# ACB-Light-R1_0-J03.net
KiCad netlist of a schematic drawn in EAGLE
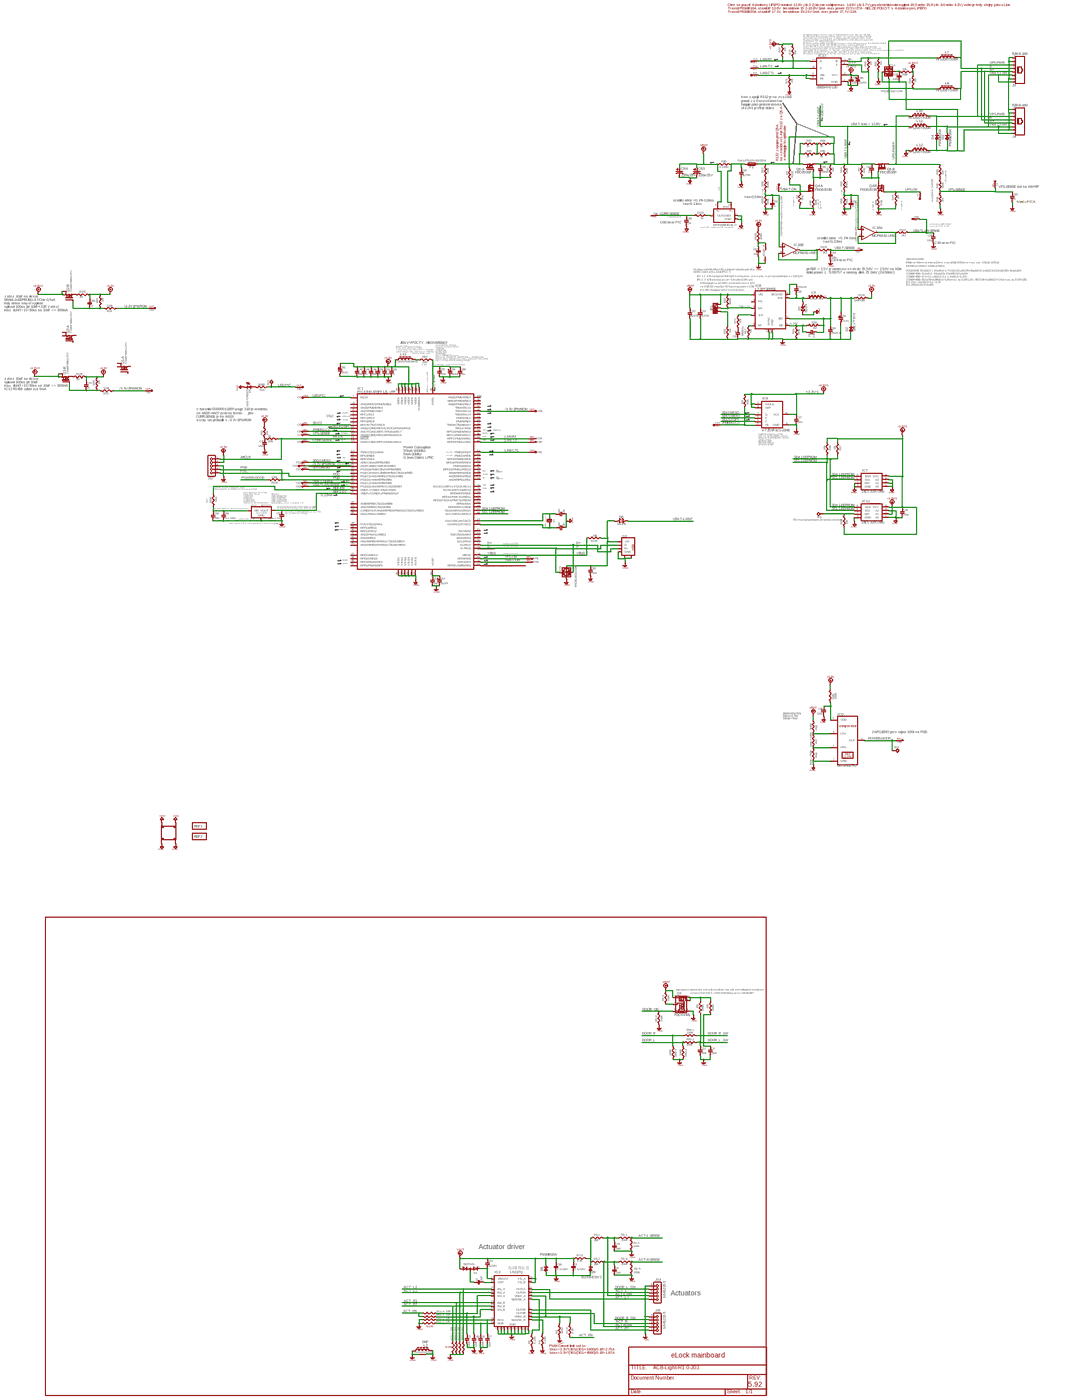
[diagram p0: schematic, sheet 1, overview]
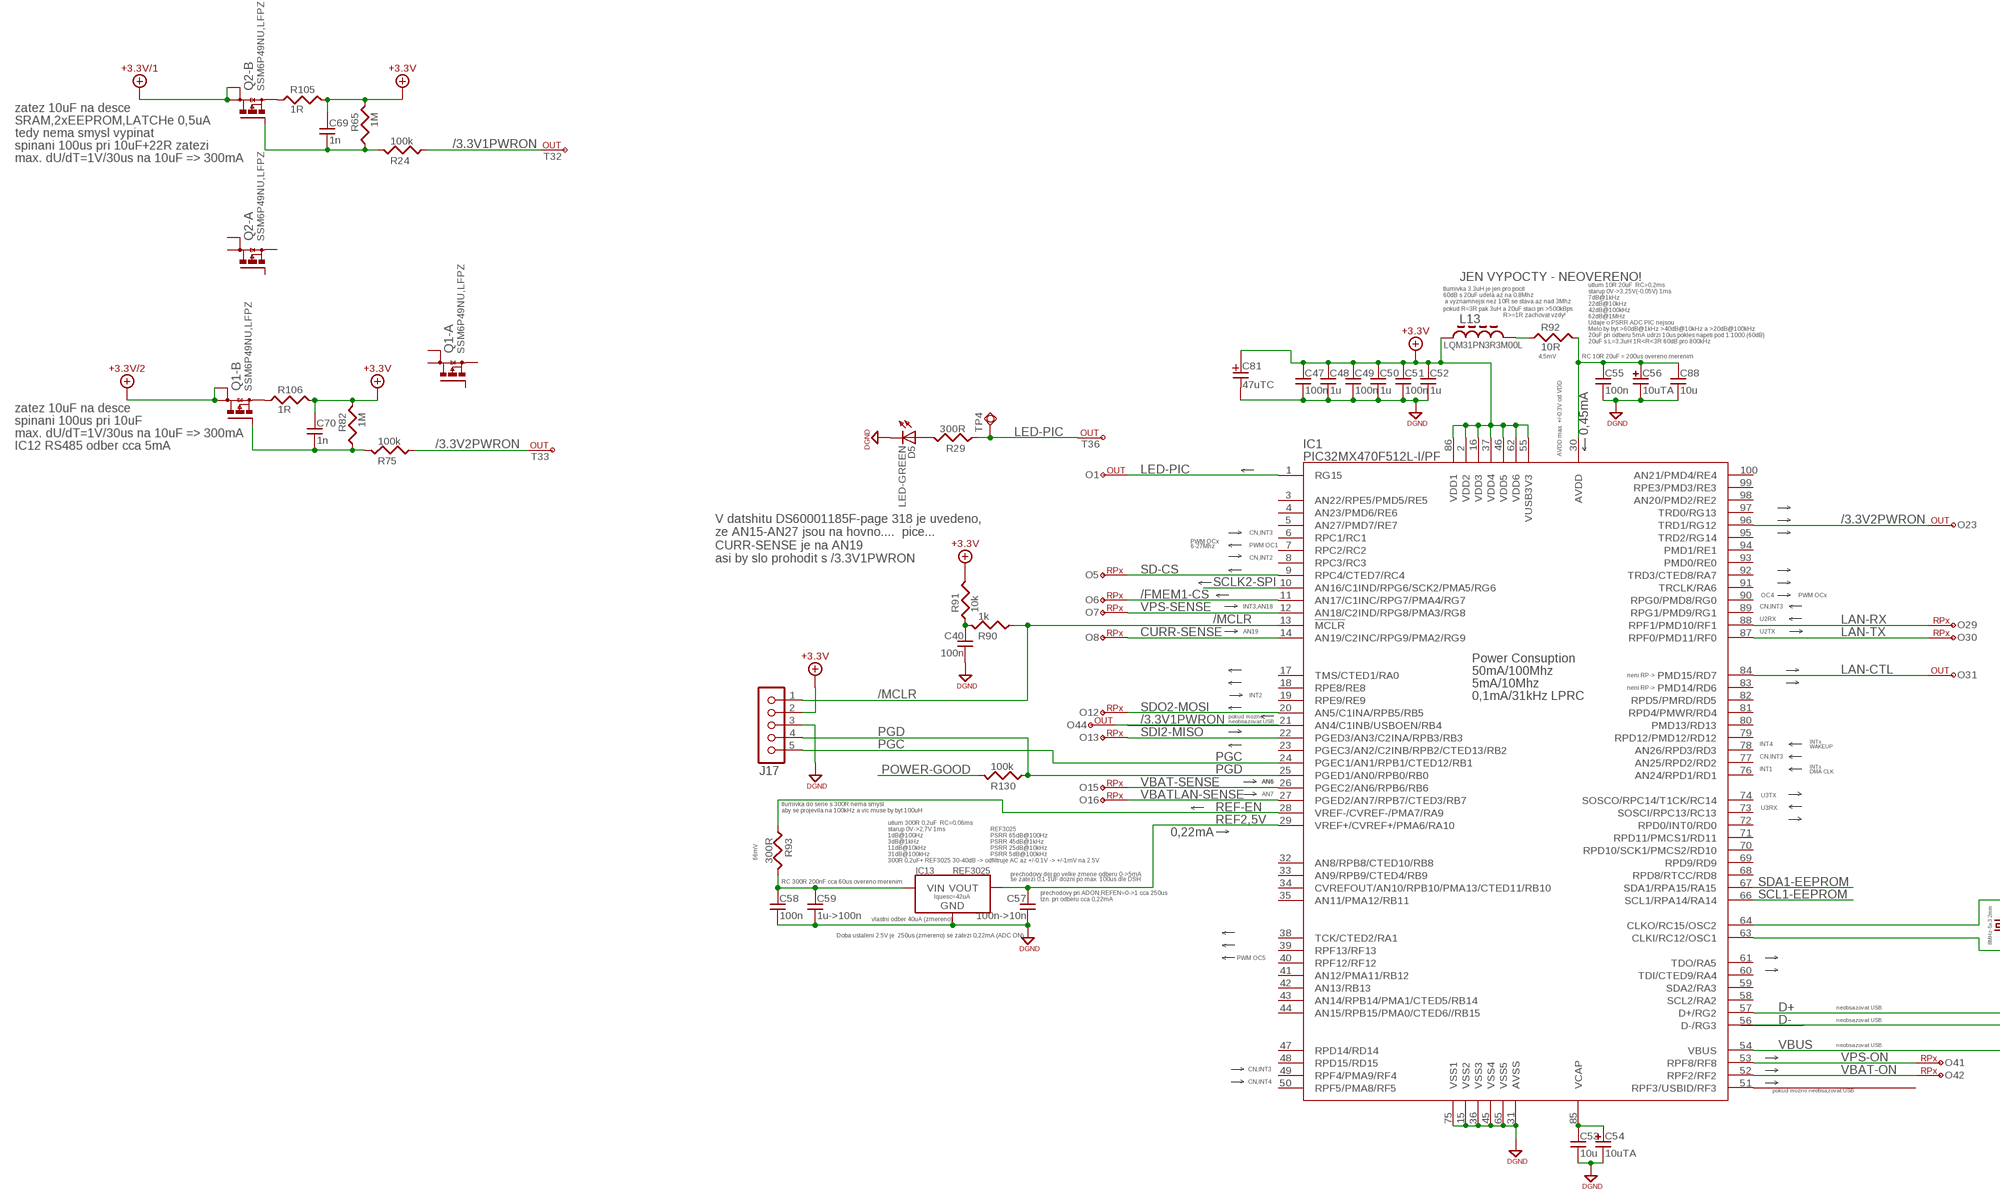
[diagram p1: schematic, sheet 1, part 1 of 5]
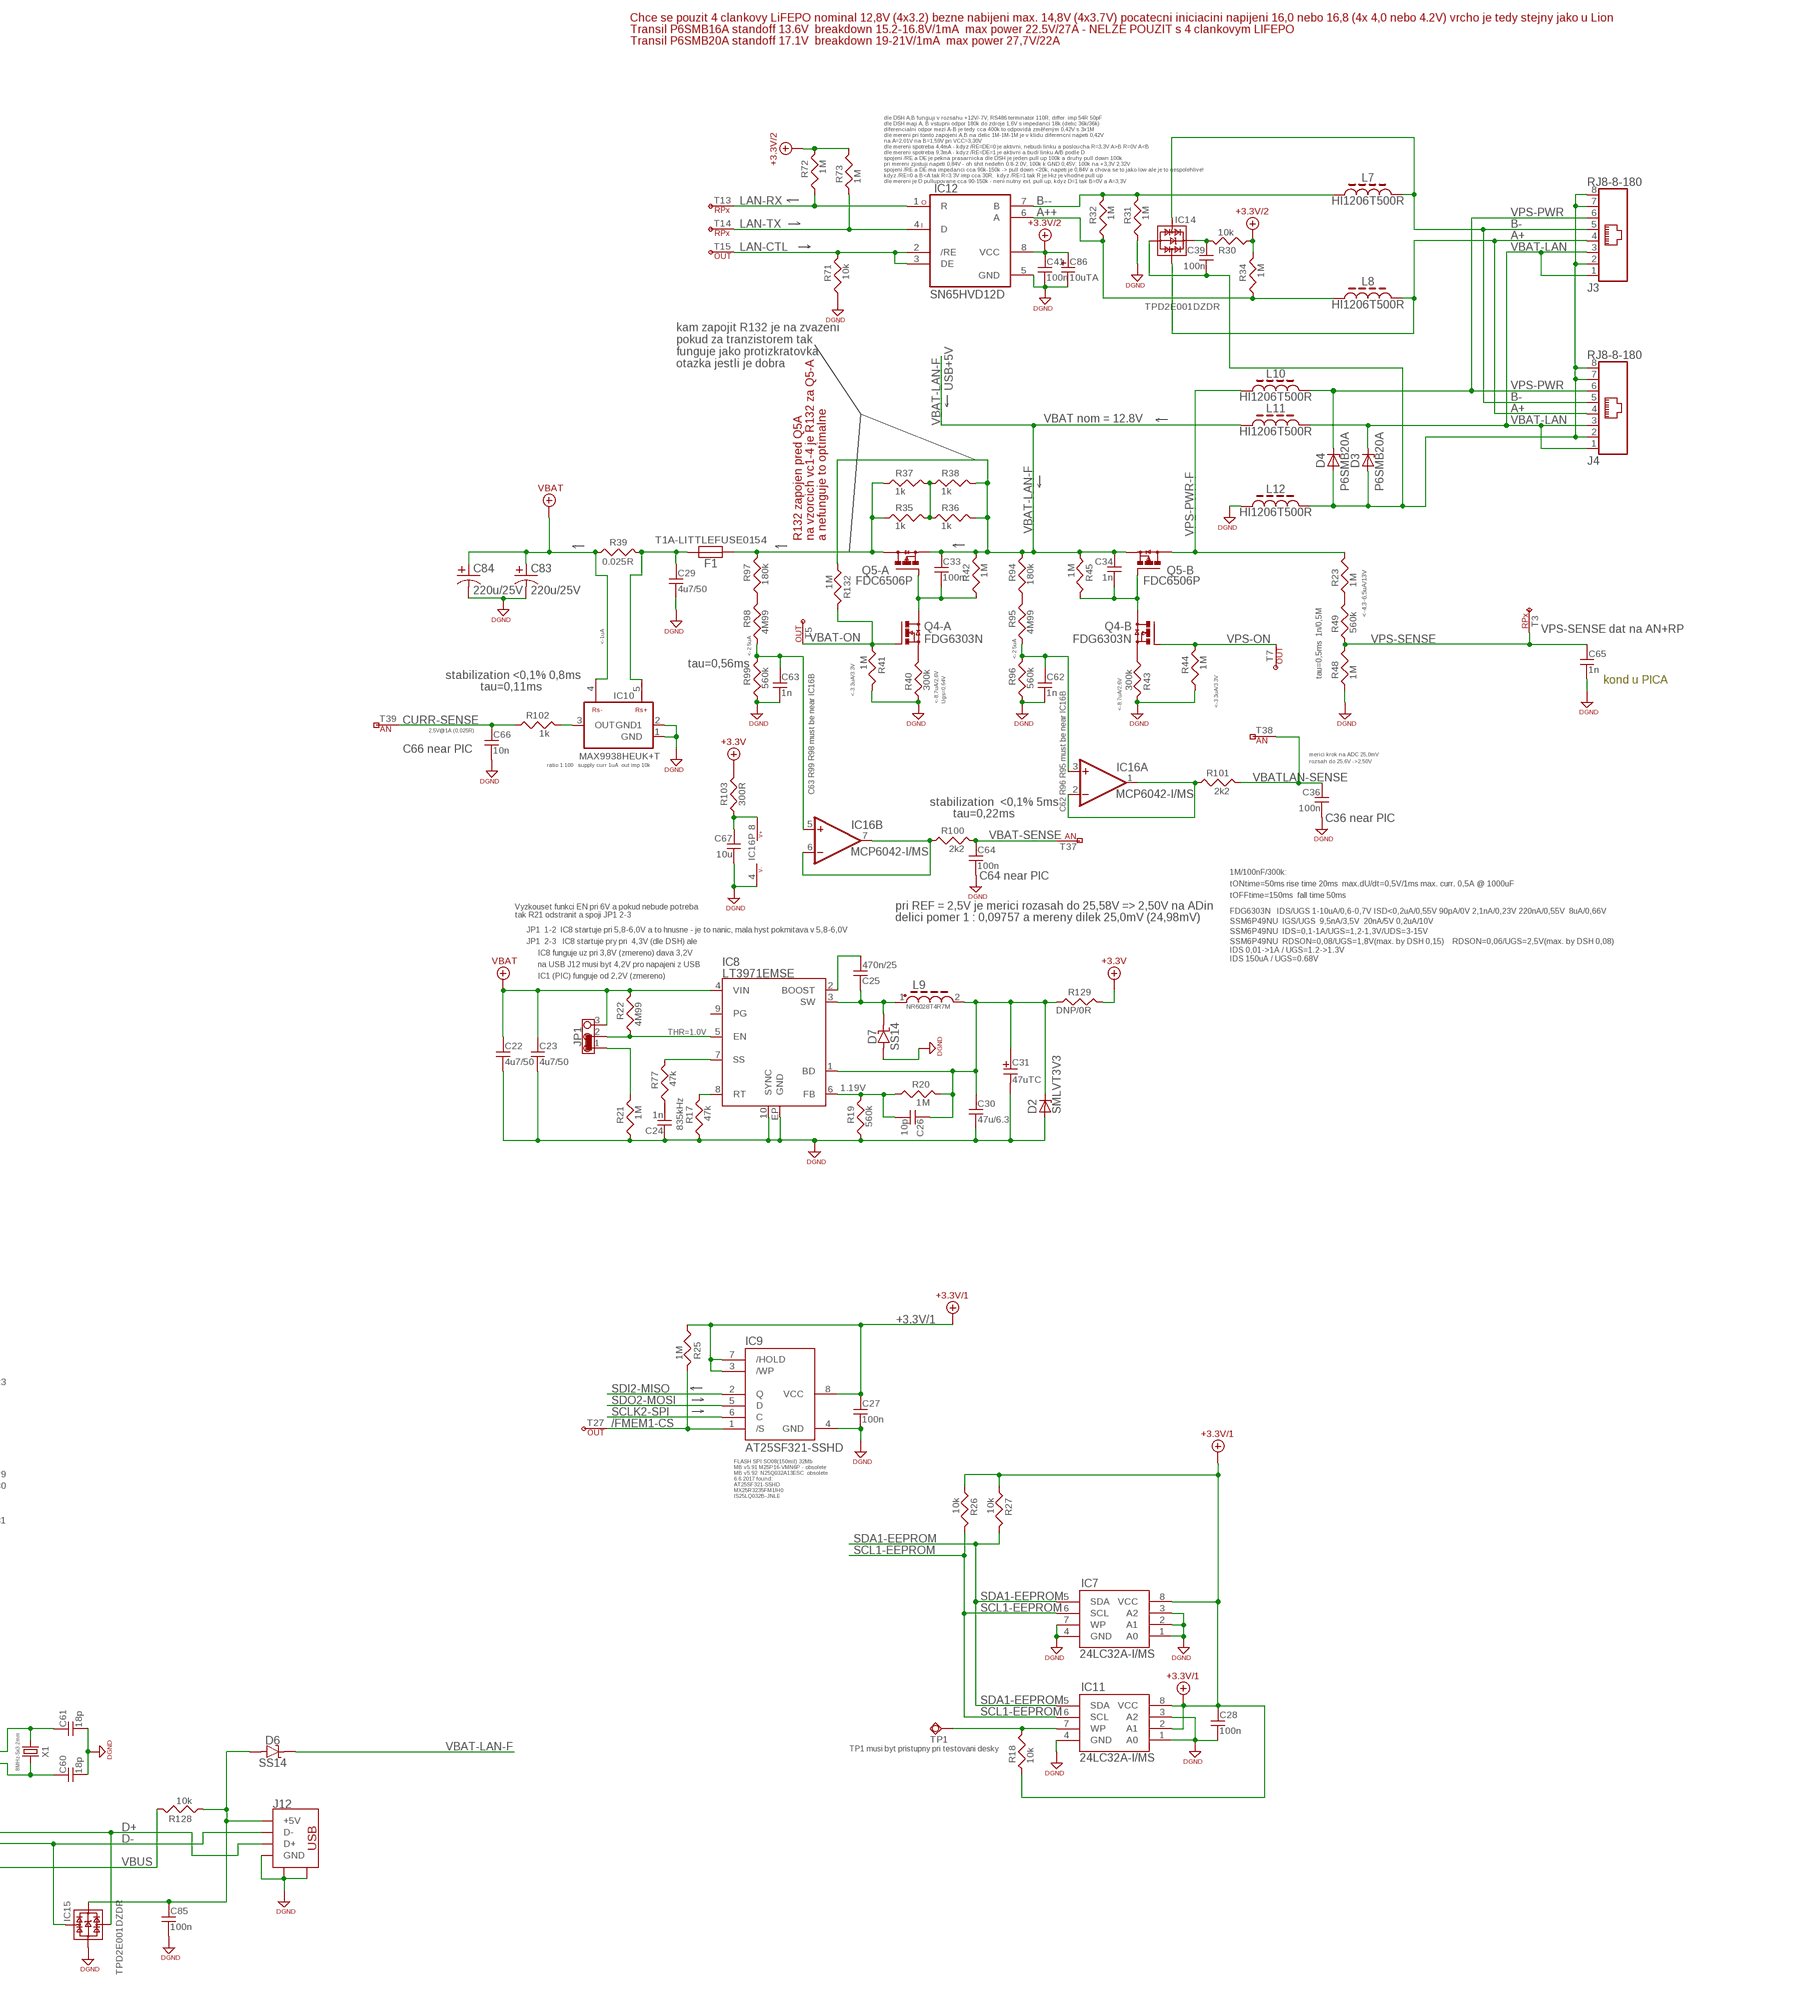
[diagram p2: schematic, sheet 1, part 2 of 5]
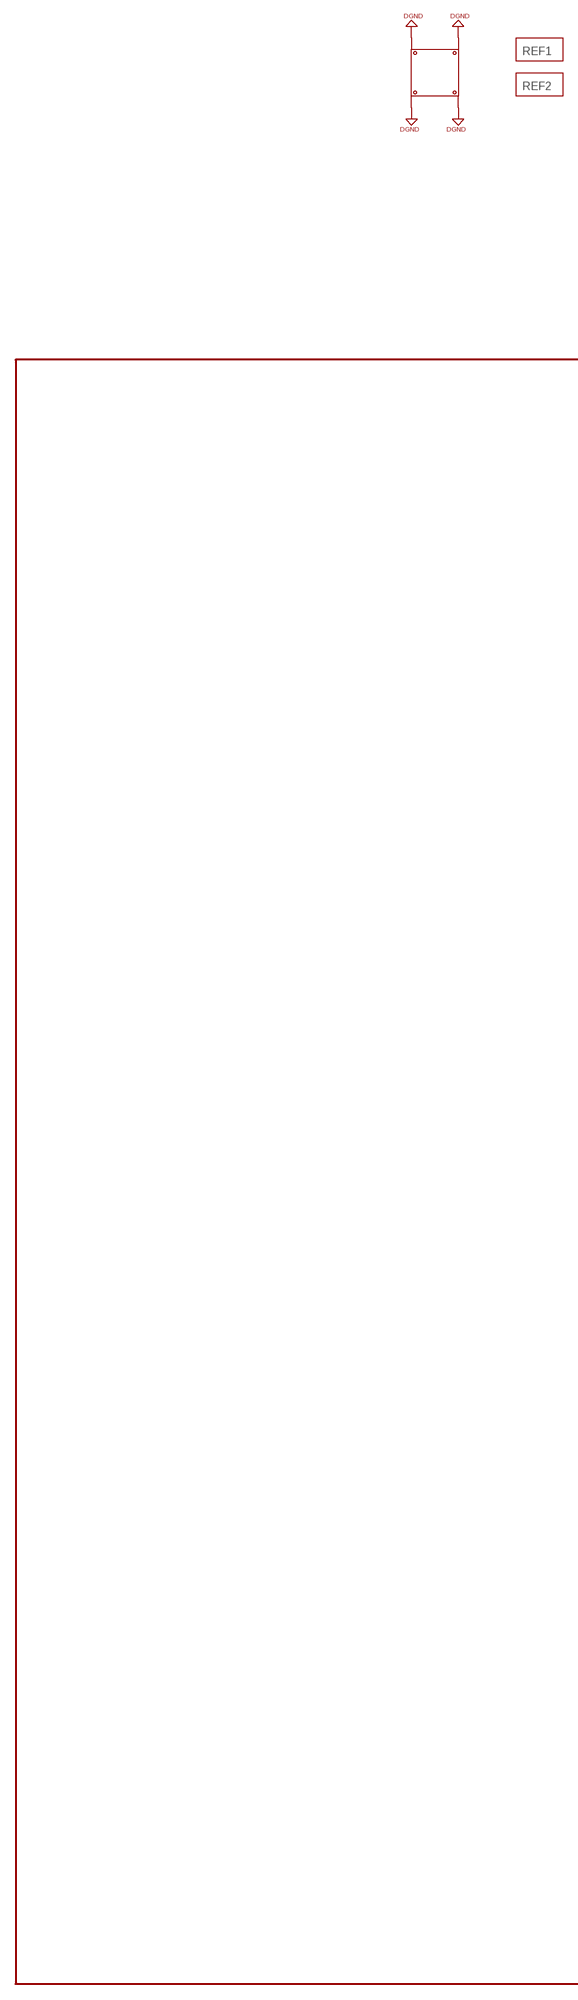
[diagram p3: schematic, sheet 1, part 3 of 5]
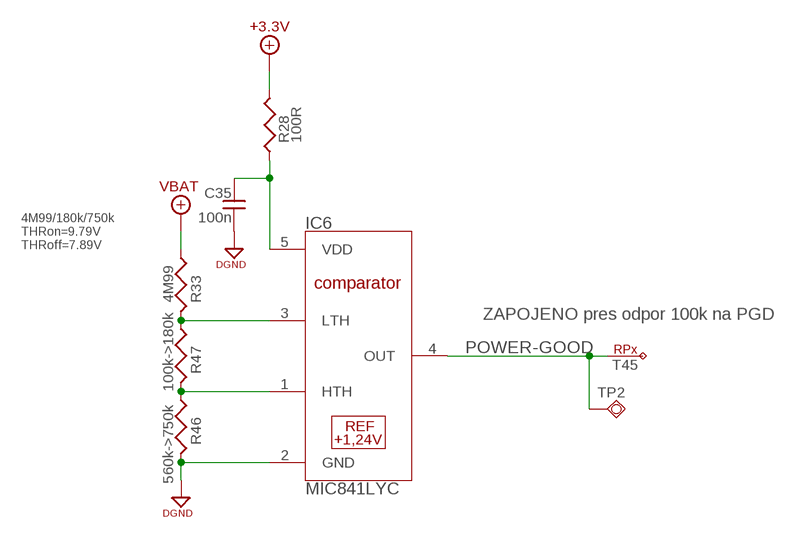
[diagram p4: schematic, sheet 1, part 4 of 5]
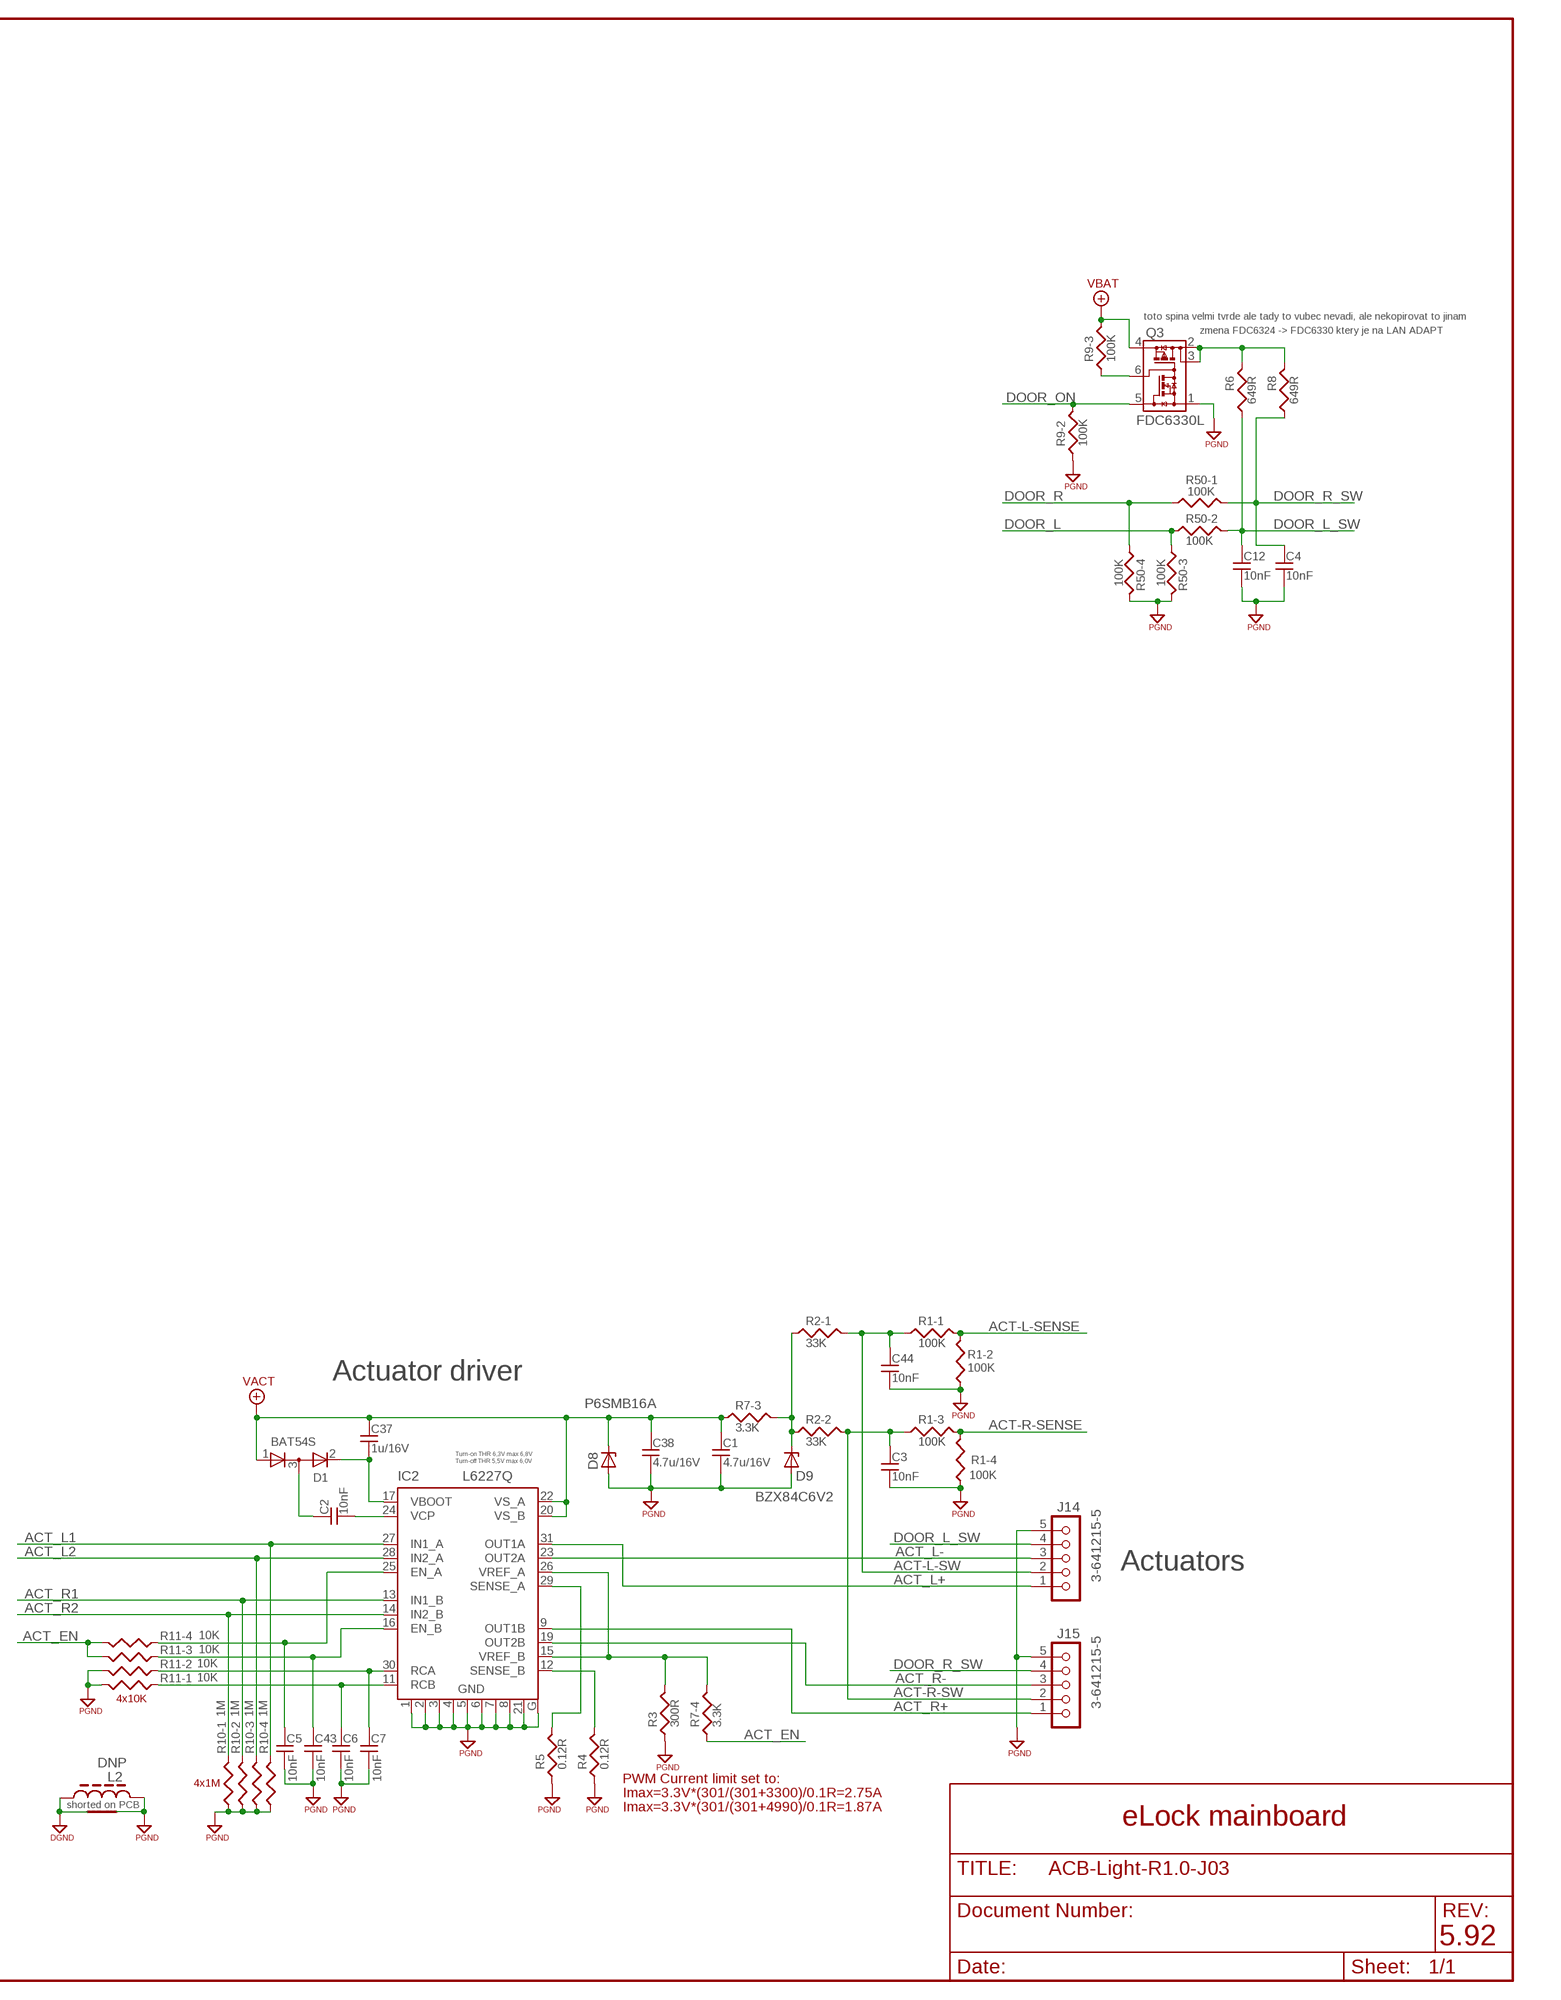
[diagram p5: schematic, sheet 1, part 5 of 5]

(export (version "E")
  (design (tool "Eeschema 10.0.6"))
  (components
    (comp (ref "C1")
      (value "4.7u/16V")
      (footprint "eagle-import:0805")
      (libsource (lib "eagle-import") (part "C-0805"))
    )
    (comp (ref "C2")
      (value "10nF")
      (footprint "eagle-import:0603")
      (libsource (lib "eagle-import") (part "C-0603"))
    )
    (comp (ref "C3")
      (value "10nF")
      (footprint "eagle-import:0603")
      (libsource (lib "eagle-import") (part "C-0603"))
    )
    (comp (ref "C4")
      (value "10nF")
      (footprint "eagle-import:0603")
      (libsource (lib "eagle-import") (part "C-0603"))
    )
    (comp (ref "C5")
      (value "10nF")
      (footprint "eagle-import:0603")
      (libsource (lib "eagle-import") (part "C-0603"))
    )
    (comp (ref "C6")
      (value "10nF")
      (footprint "eagle-import:0603")
      (libsource (lib "eagle-import") (part "C-0603"))
    )
    (comp (ref "C7")
      (value "10nF")
      (footprint "eagle-import:0603")
      (libsource (lib "eagle-import") (part "C-0603"))
    )
    (comp (ref "C12")
      (value "10nF")
      (footprint "eagle-import:0603")
      (libsource (lib "eagle-import") (part "C-0603"))
    )
    (comp (ref "C22")
      (value "4u7/50")
      (footprint "eagle-import:1206")
      (libsource (lib "eagle-import") (part "C-1206"))
    )
    (comp (ref "C23")
      (value "4u7/50")
      (footprint "eagle-import:1206")
      (libsource (lib "eagle-import") (part "C-1206"))
    )
    (comp (ref "C24")
      (value "1n")
      (footprint "eagle-import:0603")
      (libsource (lib "eagle-import") (part "C-0603"))
    )
    (comp (ref "C25")
      (value "470n/25")
      (footprint "eagle-import:0603")
      (libsource (lib "eagle-import") (part "C-0603"))
    )
    (comp (ref "C26")
      (value "10p")
      (footprint "eagle-import:0603")
      (libsource (lib "eagle-import") (part "C-0603"))
    )
    (comp (ref "C27")
      (value "100n")
      (footprint "eagle-import:0603")
      (libsource (lib "eagle-import") (part "C-0603"))
    )
    (comp (ref "C28")
      (value "100n")
      (footprint "eagle-import:0603")
      (libsource (lib "eagle-import") (part "C-0603"))
    )
    (comp (ref "C29")
      (value "4u7/50")
      (footprint "eagle-import:1206")
      (libsource (lib "eagle-import") (part "C-1206"))
    )
    (comp (ref "C30")
      (value "47u/6.3")
      (footprint "eagle-import:1206")
      (libsource (lib "eagle-import") (part "C-1206"))
    )
    (comp (ref "C31")
      (value "47uTC")
      (footprint "eagle-import:CT-C")
      (libsource (lib "eagle-import") (part "CT-C"))
    )
    (comp (ref "C33")
      (value "100n")
      (footprint "eagle-import:0603")
      (libsource (lib "eagle-import") (part "C-0603"))
    )
    (comp (ref "C34")
      (value "1n")
      (footprint "eagle-import:0603")
      (libsource (lib "eagle-import") (part "C-0603"))
    )
    (comp (ref "C35")
      (value "100n")
      (footprint "eagle-import:0603")
      (libsource (lib "eagle-import") (part "C-0603"))
    )
    (comp (ref "C36")
      (value "100n")
      (footprint "eagle-import:0603")
      (libsource (lib "eagle-import") (part "C-0603"))
    )
    (comp (ref "C37")
      (value "1u/16V")
      (footprint "eagle-import:0603")
      (libsource (lib "eagle-import") (part "C-0603"))
    )
    (comp (ref "C38")
      (value "4.7u/16V")
      (footprint "eagle-import:0805")
      (libsource (lib "eagle-import") (part "C-0805"))
    )
    (comp (ref "C39")
      (value "100n")
      (footprint "eagle-import:0603")
      (libsource (lib "eagle-import") (part "C-0603"))
    )
    (comp (ref "C40")
      (value "100n")
      (footprint "eagle-import:0603")
      (libsource (lib "eagle-import") (part "C-0603"))
    )
    (comp (ref "C41")
      (value "100n")
      (footprint "eagle-import:0603")
      (libsource (lib "eagle-import") (part "C-0603"))
    )
    (comp (ref "C43")
      (value "10nF")
      (footprint "eagle-import:0603")
      (libsource (lib "eagle-import") (part "C-0603"))
    )
    (comp (ref "C44")
      (value "10nF")
      (footprint "eagle-import:0603")
      (libsource (lib "eagle-import") (part "C-0603"))
    )
    (comp (ref "C47")
      (value "100n")
      (footprint "eagle-import:0603")
      (libsource (lib "eagle-import") (part "C-0603"))
    )
    (comp (ref "C48")
      (value "1u")
      (footprint "eagle-import:0603")
      (libsource (lib "eagle-import") (part "C-0603"))
    )
    (comp (ref "C49")
      (value "100n")
      (footprint "eagle-import:0603")
      (libsource (lib "eagle-import") (part "C-0603"))
    )
    (comp (ref "C50")
      (value "1u")
      (footprint "eagle-import:0603")
      (libsource (lib "eagle-import") (part "C-0603"))
    )
    (comp (ref "C51")
      (value "100n")
      (footprint "eagle-import:0603")
      (libsource (lib "eagle-import") (part "C-0603"))
    )
    (comp (ref "C52")
      (value "1u")
      (footprint "eagle-import:0603")
      (libsource (lib "eagle-import") (part "C-0603"))
    )
    (comp (ref "C53")
      (value "10u")
      (footprint "eagle-import:0603")
      (libsource (lib "eagle-import") (part "C-0603"))
    )
    (comp (ref "C54")
      (value "10uTA")
      (footprint "eagle-import:1206-POL-C")
      (libsource (lib "eagle-import") (part "CT-1206"))
    )
    (comp (ref "C55")
      (value "100n")
      (footprint "eagle-import:0603")
      (libsource (lib "eagle-import") (part "C-0603"))
    )
    (comp (ref "C56")
      (value "10uTA")
      (footprint "eagle-import:1206-POL-C")
      (libsource (lib "eagle-import") (part "CT-1206"))
    )
    (comp (ref "C57")
      (value "100n->10n")
      (footprint "eagle-import:0603")
      (libsource (lib "eagle-import") (part "C-0603"))
    )
    (comp (ref "C58")
      (value "100n")
      (footprint "eagle-import:0603")
      (libsource (lib "eagle-import") (part "C-0603"))
    )
    (comp (ref "C59")
      (value "1u->100n")
      (footprint "eagle-import:0603")
      (libsource (lib "eagle-import") (part "C-0603"))
    )
    (comp (ref "C60")
      (value "18p")
      (footprint "eagle-import:0603")
      (libsource (lib "eagle-import") (part "C-0603"))
    )
    (comp (ref "C61")
      (value "18p")
      (footprint "eagle-import:0603")
      (libsource (lib "eagle-import") (part "C-0603"))
    )
    (comp (ref "C62")
      (value "1n")
      (footprint "eagle-import:0603")
      (libsource (lib "eagle-import") (part "C-0603"))
    )
    (comp (ref "C63")
      (value "1n")
      (footprint "eagle-import:0603")
      (libsource (lib "eagle-import") (part "C-0603"))
    )
    (comp (ref "C64")
      (value "100n")
      (footprint "eagle-import:0603")
      (libsource (lib "eagle-import") (part "C-0603"))
    )
    (comp (ref "C65")
      (value "1n")
      (footprint "eagle-import:0603")
      (libsource (lib "eagle-import") (part "C-0603"))
    )
    (comp (ref "C66")
      (value "10n")
      (footprint "eagle-import:0603")
      (libsource (lib "eagle-import") (part "C-0603"))
    )
    (comp (ref "C67")
      (value "10u")
      (footprint "eagle-import:0603")
      (libsource (lib "eagle-import") (part "C-0603"))
    )
    (comp (ref "C69")
      (value "1n")
      (footprint "eagle-import:0603")
      (libsource (lib "eagle-import") (part "C-0603"))
    )
    (comp (ref "C70")
      (value "1n")
      (footprint "eagle-import:0603")
      (libsource (lib "eagle-import") (part "C-0603"))
    )
    (comp (ref "C81")
      (value "47uTC")
      (footprint "eagle-import:CT-C")
      (libsource (lib "eagle-import") (part "CT-C"))
    )
    (comp (ref "C83")
      (value "220u/25V")
      (footprint "eagle-import:CAP_8MM_DIA_SMT")
      (libsource (lib "eagle-import") (part "CAP-ELEC-SMD-8MM"))
    )
    (comp (ref "C84")
      (value "220u/25V")
      (footprint "eagle-import:CAP_8MM_DIA_SMT")
      (libsource (lib "eagle-import") (part "CAP-ELEC-SMD-8MM"))
    )
    (comp (ref "C85")
      (value "100n")
      (footprint "eagle-import:0603")
      (libsource (lib "eagle-import") (part "C-0603"))
    )
    (comp (ref "C86")
      (value "10uTA")
      (footprint "eagle-import:1206-POL-C")
      (libsource (lib "eagle-import") (part "CT-1206"))
    )
    (comp (ref "C88")
      (value "10u")
      (footprint "eagle-import:0603")
      (libsource (lib "eagle-import") (part "C-0603"))
    )
    (comp (ref "D1")
      (value "BAT54S")
      (footprint "eagle-import:SOT-23")
      (libsource (lib "eagle-import") (part "BAT54S"))
    )
    (comp (ref "D2")
      (value "SMLVT3V3")
      (footprint "eagle-import:SMA")
      (libsource (lib "eagle-import") (part "SMLVT3V3"))
    )
    (comp (ref "D3")
      (value "P6SMB20A")
      (footprint "eagle-import:SMB")
      (libsource (lib "eagle-import") (part "P6SMB"))
    )
    (comp (ref "D4")
      (value "P6SMB20A")
      (footprint "eagle-import:SMB")
      (libsource (lib "eagle-import") (part "P6SMB"))
    )
    (comp (ref "D5")
      (value "LED-GREEN")
      (footprint "eagle-import:0805-POL-D")
      (libsource (lib "eagle-import") (part "LED-0805"))
    )
    (comp (ref "D6")
      (value "SS14")
      (footprint "eagle-import:SMA")
      (libsource (lib "eagle-import") (part "DS-SMA"))
    )
    (comp (ref "D7")
      (value "SS14")
      (footprint "eagle-import:SMA")
      (libsource (lib "eagle-import") (part "DS-SMA"))
    )
    (comp (ref "D8")
      (value "P6SMB16A")
      (footprint "eagle-import:SMB")
      (libsource (lib "eagle-import") (part "P6SMB"))
    )
    (comp (ref "D9")
      (value "BZX84C6V2")
      (footprint "eagle-import:SOT-23")
      (libsource (lib "eagle-import") (part "BZX84C6V2"))
    )
    (comp (ref "F1")
      (value "T1A-LITTLEFUSE0154")
      (footprint "eagle-import:LITTLEFUSE0154")
      (libsource (lib "eagle-import") (part "POJISTKA-LITTLEFUSE0154"))
    )
    (comp (ref "IC1")
      (value "PIC32MX470F512L-I/PF")
      (footprint "eagle-import:TQFP100_14X14_0,5MM")
      (libsource (lib "eagle-import") (part "PIC32MX470F512L-I/PF"))
    )
    (comp (ref "IC2")
      (value "L6227Q")
      (footprint "eagle-import:SQFP-S-5X5-32")
      (libsource (lib "eagle-import") (part "L6227Q"))
    )
    (comp (ref "IC6")
      (value "MIC841LYC")
      (footprint "eagle-import:SC-70-5")
      (libsource (lib "eagle-import") (part "MIC841LYC"))
    )
    (comp (ref "IC7")
      (value "24LC32A-I/MS")
      (footprint "eagle-import:MSOP-08")
      (libsource (lib "eagle-import") (part "24-I/MS"))
    )
    (comp (ref "IC8")
      (value "LT3971EMSE")
      (footprint "eagle-import:MSOP10EXP")
      (libsource (lib "eagle-import") (part "LT3971EMSE"))
    )
    (comp (ref "IC9")
      (value "AT25SF321-SSHD")
      (footprint "eagle-import:SO-08")
      (libsource (lib "eagle-import") (part "M25P16-VMN6P"))
    )
    (comp (ref "IC10")
      (value "MAX9938HEUK+T")
      (footprint "eagle-import:SOT23-5")
      (libsource (lib "eagle-import") (part "TSM9938HEUK+T"))
    )
    (comp (ref "IC11")
      (value "24LC32A-I/MS")
      (footprint "eagle-import:MSOP-08")
      (libsource (lib "eagle-import") (part "24-I/MS"))
    )
    (comp (ref "IC12")
      (value "SN65HVD12D")
      (footprint "eagle-import:SO08")
      (libsource (lib "eagle-import") (part "SN65HVD3082ED"))
    )
    (comp (ref "IC13")
      (value "REF3025")
      (footprint "eagle-import:SOT23")
      (libsource (lib "eagle-import") (part "REF3025"))
    )
    (comp (ref "IC14")
      (value "TPD2E001DZDR")
      (footprint "eagle-import:SOT-143")
      (libsource (lib "eagle-import") (part "SR05.TCT"))
    )
    (comp (ref "IC15")
      (value "TPD2E001DZDR")
      (footprint "eagle-import:SOT-143")
      (libsource (lib "eagle-import") (part "SR05.TCT"))
    )
    (comp (ref "IC16")
      (value "MCP6042-I/MS")
      (footprint "eagle-import:MSOP-08")
      (libsource (lib "eagle-import") (part "MCP6042-I/MS"))
    )
    (comp (ref "J3")
      (value "RJ8-8-180")
      (footprint "eagle-import:RJ8-8-180")
      (libsource (lib "eagle-import") (part "RJ8-8-180"))
    )
    (comp (ref "J4")
      (value "RJ8-8-180")
      (footprint "eagle-import:RJ8-8-180")
      (libsource (lib "eagle-import") (part "RJ8-8-180"))
    )
    (comp (ref "J12")
      (value "USB_A_180")
      (footprint "eagle-import:USB_B_180")
      (libsource (lib "eagle-import") (part "USB_B_180"))
    )
    (comp (ref "J14")
      (value "3-641215-5")
      (footprint "eagle-import:3-641215-5")
      (libsource (lib "eagle-import") (part "3-641215-5"))
    )
    (comp (ref "J15")
      (value "3-641215-5")
      (footprint "eagle-import:3-641215-5")
      (libsource (lib "eagle-import") (part "3-641215-5"))
    )
    (comp (ref "J17")
      (value "DNP-open-hole")
      (footprint "eagle-import:MA05-1")
      (libsource (lib "eagle-import") (part "MA05-1"))
    )
    (comp (ref "JP1")
      (value "JP3CLOSE12")
      (footprint "eagle-import:JP3CLOSE12")
      (libsource (lib "eagle-import") (part "JP3CLOSE12"))
    )
    (comp (ref "L2")
      (value "DNP")
      (footprint "eagle-import:0805-0RTOP")
      (libsource (lib "eagle-import") (part "L-0805-0R"))
    )
    (comp (ref "L7")
      (value "HI1206T500R")
      (footprint "eagle-import:1206")
      (libsource (lib "eagle-import") (part "L-1206"))
    )
    (comp (ref "L8")
      (value "HI1206T500R")
      (footprint "eagle-import:1206")
      (libsource (lib "eagle-import") (part "L-1206"))
    )
    (comp (ref "L9")
      (value "NR6028T4R7M")
      (footprint "eagle-import:NR6028")
      (libsource (lib "eagle-import") (part "NR6028"))
    )
    (comp (ref "L10")
      (value "HI1206T500R")
      (footprint "eagle-import:1206")
      (libsource (lib "eagle-import") (part "L-1206"))
    )
    (comp (ref "L11")
      (value "HI1206T500R")
      (footprint "eagle-import:1206")
      (libsource (lib "eagle-import") (part "L-1206"))
    )
    (comp (ref "L12")
      (value "HI1206T500R")
      (footprint "eagle-import:1206")
      (libsource (lib "eagle-import") (part "L-1206"))
    )
    (comp (ref "L13")
      (value "LQM31PN3R3M00L")
      (footprint "eagle-import:1206")
      (libsource (lib "eagle-import") (part "L-1206"))
    )
    (comp (ref "O1")
      (value "PIC-OUT")
      (footprint "eagle-import:TEMP-PAD")
      (libsource (lib "eagle-import") (part "PIC-OUT"))
    )
    (comp (ref "O5")
      (value "PIC-RPX")
      (footprint "eagle-import:TEMP-PAD")
      (libsource (lib "eagle-import") (part "PIC-RPX"))
    )
    (comp (ref "O6")
      (value "PIC-RPX")
      (footprint "eagle-import:TEMP-PAD")
      (libsource (lib "eagle-import") (part "PIC-RPX"))
    )
    (comp (ref "O7")
      (value "PIC-RPX")
      (footprint "eagle-import:TEMP-PAD")
      (libsource (lib "eagle-import") (part "PIC-RPX"))
    )
    (comp (ref "O8")
      (value "PIC-RPX")
      (footprint "eagle-import:TEMP-PAD")
      (libsource (lib "eagle-import") (part "PIC-RPX"))
    )
    (comp (ref "O12")
      (value "PIC-RPX")
      (footprint "eagle-import:TEMP-PAD")
      (libsource (lib "eagle-import") (part "PIC-RPX"))
    )
    (comp (ref "O13")
      (value "PIC-RPX")
      (footprint "eagle-import:TEMP-PAD")
      (libsource (lib "eagle-import") (part "PIC-RPX"))
    )
    (comp (ref "O15")
      (value "PIC-RPX")
      (footprint "eagle-import:TEMP-PAD")
      (libsource (lib "eagle-import") (part "PIC-RPX"))
    )
    (comp (ref "O16")
      (value "PIC-RPX")
      (footprint "eagle-import:TEMP-PAD")
      (libsource (lib "eagle-import") (part "PIC-RPX"))
    )
    (comp (ref "O23")
      (value "PIC-OUT")
      (footprint "eagle-import:TEMP-PAD")
      (libsource (lib "eagle-import") (part "PIC-OUT"))
    )
    (comp (ref "O29")
      (value "PIC-RPX")
      (footprint "eagle-import:TEMP-PAD")
      (libsource (lib "eagle-import") (part "PIC-RPX"))
    )
    (comp (ref "O30")
      (value "PIC-RPX")
      (footprint "eagle-import:TEMP-PAD")
      (libsource (lib "eagle-import") (part "PIC-RPX"))
    )
    (comp (ref "O31")
      (value "PIC-OUT")
      (footprint "eagle-import:TEMP-PAD")
      (libsource (lib "eagle-import") (part "PIC-OUT"))
    )
    (comp (ref "O41")
      (value "PIC-RPX")
      (footprint "eagle-import:TEMP-PAD")
      (libsource (lib "eagle-import") (part "PIC-RPX"))
    )
    (comp (ref "O42")
      (value "PIC-RPX")
      (footprint "eagle-import:TEMP-PAD")
      (libsource (lib "eagle-import") (part "PIC-RPX"))
    )
    (comp (ref "O44")
      (value "PIC-OUT")
      (footprint "eagle-import:TEMP-PAD")
      (libsource (lib "eagle-import") (part "PIC-OUT"))
    )
    (comp (ref "PCB1")
      (value "PCB-ACB")
      (footprint "eagle-import:PCB-ACB")
      (libsource (lib "eagle-import") (part "PCB-ACB-1"))
    )
    (comp (ref "Q1")
      (value "SSM6P49NU,LFPZ")
      (footprint "eagle-import:MICRO_FET")
      (libsource (lib "eagle-import") (part "SSM6P49PZNU,LF"))
    )
    (comp (ref "Q2")
      (value "SSM6P49NU,LFPZ")
      (footprint "eagle-import:MICRO_FET")
      (libsource (lib "eagle-import") (part "SSM6P49PZNU,LF"))
    )
    (comp (ref "Q3")
      (value "FDC6330L")
      (footprint "eagle-import:SSOT-6@2")
      (libsource (lib "eagle-import") (part "FDC6324L"))
    )
    (comp (ref "Q4")
      (value "FDG6303N")
      (footprint "eagle-import:SC70-6")
      (libsource (lib "eagle-import") (part "FDG6303N"))
    )
    (comp (ref "Q5")
      (value "FDC6506P")
      (footprint "eagle-import:SSOT-6")
      (libsource (lib "eagle-import") (part "FDC6506D"))
    )
    (comp (ref "R1")
      (value "100K")
      (footprint "eagle-import:0603-ARRAY")
      (libsource (lib "eagle-import") (part "EXB-38"))
    )
    (comp (ref "R2")
      (value "33K")
      (footprint "eagle-import:0603-ARRAY")
      (libsource (lib "eagle-import") (part "EXB-38"))
    )
    (comp (ref "R3")
      (value "300R")
      (footprint "eagle-import:0603")
      (libsource (lib "eagle-import") (part "R-0603"))
    )
    (comp (ref "R4")
      (value "0.12R")
      (footprint "eagle-import:0805")
      (libsource (lib "eagle-import") (part "R-0805"))
    )
    (comp (ref "R5")
      (value "0.12R")
      (footprint "eagle-import:0805")
      (libsource (lib "eagle-import") (part "R-0805"))
    )
    (comp (ref "R6")
      (value "649R")
      (footprint "eagle-import:0603")
      (libsource (lib "eagle-import") (part "R-0603"))
    )
    (comp (ref "R7")
      (value "3.3K")
      (footprint "eagle-import:0603-ARRAY")
      (libsource (lib "eagle-import") (part "EXB-38"))
    )
    (comp (ref "R8")
      (value "649R")
      (footprint "eagle-import:0603")
      (libsource (lib "eagle-import") (part "R-0603"))
    )
    (comp (ref "R9")
      (value "100K")
      (footprint "eagle-import:0603-ARRAY")
      (libsource (lib "eagle-import") (part "EXB-38"))
    )
    (comp (ref "R10")
      (value "1M")
      (footprint "eagle-import:0603-ARRAY")
      (libsource (lib "eagle-import") (part "EXB-38"))
    )
    (comp (ref "R11")
      (value "10K")
      (footprint "eagle-import:0603-ARRAY")
      (libsource (lib "eagle-import") (part "EXB-38"))
    )
    (comp (ref "R17")
      (value "47k")
      (footprint "eagle-import:0603")
      (libsource (lib "eagle-import") (part "R-0603"))
    )
    (comp (ref "R18")
      (value "10k")
      (footprint "eagle-import:0603")
      (libsource (lib "eagle-import") (part "R-0603"))
    )
    (comp (ref "R19")
      (value "560k")
      (footprint "eagle-import:0603")
      (libsource (lib "eagle-import") (part "R-0603"))
    )
    (comp (ref "R20")
      (value "1M")
      (footprint "eagle-import:0603")
      (libsource (lib "eagle-import") (part "R-0603"))
    )
    (comp (ref "R21")
      (value "1M")
      (footprint "eagle-import:0603")
      (libsource (lib "eagle-import") (part "R-0603"))
    )
    (comp (ref "R22")
      (value "4M99")
      (footprint "eagle-import:0603")
      (libsource (lib "eagle-import") (part "R-0603"))
    )
    (comp (ref "R23")
      (value "1M")
      (footprint "eagle-import:0603")
      (libsource (lib "eagle-import") (part "R-0603"))
    )
    (comp (ref "R24")
      (value "100k")
      (footprint "eagle-import:0603")
      (libsource (lib "eagle-import") (part "R-0603"))
    )
    (comp (ref "R25")
      (value "1M")
      (footprint "eagle-import:0603")
      (libsource (lib "eagle-import") (part "R-0603"))
    )
    (comp (ref "R26")
      (value "10k")
      (footprint "eagle-import:0603")
      (libsource (lib "eagle-import") (part "R-0603"))
    )
    (comp (ref "R27")
      (value "10k")
      (footprint "eagle-import:0603")
      (libsource (lib "eagle-import") (part "R-0603"))
    )
    (comp (ref "R28")
      (value "100R")
      (footprint "eagle-import:0603")
      (libsource (lib "eagle-import") (part "R-0603"))
    )
    (comp (ref "R29")
      (value "300R")
      (footprint "eagle-import:0603")
      (libsource (lib "eagle-import") (part "R-0603"))
    )
    (comp (ref "R30")
      (value "10k")
      (footprint "eagle-import:0603")
      (libsource (lib "eagle-import") (part "R-0603"))
    )
    (comp (ref "R31")
      (value "1M")
      (footprint "eagle-import:0603")
      (libsource (lib "eagle-import") (part "R-0603"))
    )
    (comp (ref "R32")
      (value "1M")
      (footprint "eagle-import:0603")
      (libsource (lib "eagle-import") (part "R-0603"))
    )
    (comp (ref "R33")
      (value "4M99")
      (footprint "eagle-import:0603")
      (libsource (lib "eagle-import") (part "R-0603"))
    )
    (comp (ref "R34")
      (value "1M")
      (footprint "eagle-import:0603")
      (libsource (lib "eagle-import") (part "R-0603"))
    )
    (comp (ref "R35")
      (value "1k")
      (footprint "eagle-import:0805")
      (libsource (lib "eagle-import") (part "R-0805"))
    )
    (comp (ref "R36")
      (value "1k")
      (footprint "eagle-import:0805")
      (libsource (lib "eagle-import") (part "R-0805"))
    )
    (comp (ref "R37")
      (value "1k")
      (footprint "eagle-import:0805")
      (libsource (lib "eagle-import") (part "R-0805"))
    )
    (comp (ref "R38")
      (value "1k")
      (footprint "eagle-import:0805")
      (libsource (lib "eagle-import") (part "R-0805"))
    )
    (comp (ref "R39")
      (value "0.025R")
      (footprint "eagle-import:0805")
      (libsource (lib "eagle-import") (part "R-0805"))
    )
    (comp (ref "R40")
      (value "300k")
      (footprint "eagle-import:0603")
      (libsource (lib "eagle-import") (part "R-0603"))
    )
    (comp (ref "R41")
      (value "1M")
      (footprint "eagle-import:0603")
      (libsource (lib "eagle-import") (part "R-0603"))
    )
    (comp (ref "R42")
      (value "1M")
      (footprint "eagle-import:0603")
      (libsource (lib "eagle-import") (part "R-0603"))
    )
    (comp (ref "R43")
      (value "300k")
      (footprint "eagle-import:0603")
      (libsource (lib "eagle-import") (part "R-0603"))
    )
    (comp (ref "R44")
      (value "1M")
      (footprint "eagle-import:0603")
      (libsource (lib "eagle-import") (part "R-0603"))
    )
    (comp (ref "R45")
      (value "1M")
      (footprint "eagle-import:0603")
      (libsource (lib "eagle-import") (part "R-0603"))
    )
    (comp (ref "R46")
      (value "560k->750k")
      (footprint "eagle-import:0603")
      (libsource (lib "eagle-import") (part "R-0603"))
    )
    (comp (ref "R47")
      (value "100k->180k")
      (footprint "eagle-import:0603")
      (libsource (lib "eagle-import") (part "R-0603"))
    )
    (comp (ref "R48")
      (value "1M")
      (footprint "eagle-import:0603")
      (libsource (lib "eagle-import") (part "R-0603"))
    )
    (comp (ref "R49")
      (value "560k")
      (footprint "eagle-import:0603")
      (libsource (lib "eagle-import") (part "R-0603"))
    )
    (comp (ref "R50")
      (value "100K")
      (footprint "eagle-import:0603-ARRAY")
      (libsource (lib "eagle-import") (part "EXB-38"))
    )
    (comp (ref "R65")
      (value "1M")
      (footprint "eagle-import:0603")
      (libsource (lib "eagle-import") (part "R-0603"))
    )
    (comp (ref "R71")
      (value "10k")
      (footprint "eagle-import:0603")
      (libsource (lib "eagle-import") (part "R-0603"))
    )
    (comp (ref "R72")
      (value "1M")
      (footprint "eagle-import:0603")
      (libsource (lib "eagle-import") (part "R-0603"))
    )
    (comp (ref "R73")
      (value "1M")
      (footprint "eagle-import:0603")
      (libsource (lib "eagle-import") (part "R-0603"))
    )
    (comp (ref "R75")
      (value "100k")
      (footprint "eagle-import:0603")
      (libsource (lib "eagle-import") (part "R-0603"))
    )
    (comp (ref "R77")
      (value "47k")
      (footprint "eagle-import:0603")
      (libsource (lib "eagle-import") (part "R-0603"))
    )
    (comp (ref "R82")
      (value "1M")
      (footprint "eagle-import:0603")
      (libsource (lib "eagle-import") (part "R-0603"))
    )
    (comp (ref "R90")
      (value "1k")
      (footprint "eagle-import:0603")
      (libsource (lib "eagle-import") (part "R-0603"))
    )
    (comp (ref "R91")
      (value "10k")
      (footprint "eagle-import:0603")
      (libsource (lib "eagle-import") (part "R-0603"))
    )
    (comp (ref "R92")
      (value "10R")
      (footprint "eagle-import:0603")
      (libsource (lib "eagle-import") (part "R-0603"))
    )
    (comp (ref "R93")
      (value "300R")
      (footprint "eagle-import:0603")
      (libsource (lib "eagle-import") (part "R-0603"))
    )
    (comp (ref "R94")
      (value "180k")
      (footprint "eagle-import:0603")
      (libsource (lib "eagle-import") (part "R-0603"))
    )
    (comp (ref "R95")
      (value "4M99")
      (footprint "eagle-import:0603")
      (libsource (lib "eagle-import") (part "R-0603"))
    )
    (comp (ref "R96")
      (value "560k")
      (footprint "eagle-import:0603")
      (libsource (lib "eagle-import") (part "R-0603"))
    )
    (comp (ref "R97")
      (value "180k")
      (footprint "eagle-import:0603")
      (libsource (lib "eagle-import") (part "R-0603"))
    )
    (comp (ref "R98")
      (value "4M99")
      (footprint "eagle-import:0603")
      (libsource (lib "eagle-import") (part "R-0603"))
    )
    (comp (ref "R99")
      (value "560k")
      (footprint "eagle-import:0603")
      (libsource (lib "eagle-import") (part "R-0603"))
    )
    (comp (ref "R100")
      (value "2k2")
      (footprint "eagle-import:0603")
      (libsource (lib "eagle-import") (part "R-0603"))
    )
    (comp (ref "R101")
      (value "2k2")
      (footprint "eagle-import:0603")
      (libsource (lib "eagle-import") (part "R-0603"))
    )
    (comp (ref "R102")
      (value "1k")
      (footprint "eagle-import:0603")
      (libsource (lib "eagle-import") (part "R-0603"))
    )
    (comp (ref "R103")
      (value "300R")
      (footprint "eagle-import:0603")
      (libsource (lib "eagle-import") (part "R-0603"))
    )
    (comp (ref "R105")
      (value "1R")
      (footprint "eagle-import:0805")
      (libsource (lib "eagle-import") (part "R-0805"))
    )
    (comp (ref "R106")
      (value "1R")
      (footprint "eagle-import:0805")
      (libsource (lib "eagle-import") (part "R-0805"))
    )
    (comp (ref "R128")
      (value "10k")
      (footprint "eagle-import:0603")
      (libsource (lib "eagle-import") (part "R-0603"))
    )
    (comp (ref "R129")
      (value "DNP/0R")
      (footprint "eagle-import:0603")
      (libsource (lib "eagle-import") (part "R-0603"))
    )
    (comp (ref "R130")
      (value "100k")
      (footprint "eagle-import:0603")
      (libsource (lib "eagle-import") (part "R-0603"))
    )
    (comp (ref "R132")
      (value "1M")
      (footprint "eagle-import:0603")
      (libsource (lib "eagle-import") (part "R-0603"))
    )
    (comp (ref "REF1")
      (value "REF")
      (footprint "eagle-import:REF")
      (libsource (lib "eagle-import") (part "REF"))
    )
    (comp (ref "REF2")
      (value "REF")
      (footprint "eagle-import:REF")
      (libsource (lib "eagle-import") (part "REF"))
    )
    (comp (ref "T3")
      (value "PIC-RPX")
      (footprint "eagle-import:TEMP-PAD")
      (libsource (lib "eagle-import") (part "PIC-RPX"))
    )
    (comp (ref "T5")
      (value "PIC-OUT")
      (footprint "eagle-import:TEMP-PAD")
      (libsource (lib "eagle-import") (part "PIC-OUT"))
    )
    (comp (ref "T7")
      (value "PIC-OUT")
      (footprint "eagle-import:TEMP-PAD")
      (libsource (lib "eagle-import") (part "PIC-OUT"))
    )
    (comp (ref "T13")
      (value "PIC-RPX")
      (footprint "eagle-import:TEMP-PAD")
      (libsource (lib "eagle-import") (part "PIC-RPX"))
    )
    (comp (ref "T14")
      (value "PIC-RPX")
      (footprint "eagle-import:TEMP-PAD")
      (libsource (lib "eagle-import") (part "PIC-RPX"))
    )
    (comp (ref "T15")
      (value "PIC-OUT")
      (footprint "eagle-import:TEMP-PAD")
      (libsource (lib "eagle-import") (part "PIC-OUT"))
    )
    (comp (ref "T27")
      (value "PIC-OUT")
      (footprint "eagle-import:TEMP-PAD")
      (libsource (lib "eagle-import") (part "PIC-OUT"))
    )
    (comp (ref "T32")
      (value "PIC-OUT")
      (footprint "eagle-import:TEMP-PAD")
      (libsource (lib "eagle-import") (part "PIC-OUT"))
    )
    (comp (ref "T33")
      (value "PIC-OUT")
      (footprint "eagle-import:TEMP-PAD")
      (libsource (lib "eagle-import") (part "PIC-OUT"))
    )
    (comp (ref "T36")
      (value "PIC-OUT")
      (footprint "eagle-import:TEMP-PAD")
      (libsource (lib "eagle-import") (part "PIC-OUT"))
    )
    (comp (ref "T37")
      (value "PIN-AN")
      (footprint "eagle-import:TEMP-PAD")
      (libsource (lib "eagle-import") (part "PIN-AN"))
    )
    (comp (ref "T38")
      (value "PIN-AN")
      (footprint "eagle-import:TEMP-PAD")
      (libsource (lib "eagle-import") (part "PIN-AN"))
    )
    (comp (ref "T39")
      (value "PIN-AN")
      (footprint "eagle-import:TEMP-PAD")
      (libsource (lib "eagle-import") (part "PIN-AN"))
    )
    (comp (ref "T45")
      (value "PIC-RPX")
      (footprint "eagle-import:TEMP-PAD")
      (libsource (lib "eagle-import") (part "PIC-RPX"))
    )
    (comp (ref "TP1")
      (value "DNP-TestPoint")
      (footprint "eagle-import:SMD_ROUND_1MM")
      (libsource (lib "eagle-import") (part "ROUND_SMD1MM"))
    )
    (comp (ref "TP2")
      (value "DNP-TestPoint")
      (footprint "eagle-import:TH_ROUND_14MM08MM")
      (libsource (lib "eagle-import") (part "ROUND_SMDTH1.4MM"))
    )
    (comp (ref "TP4")
      (value "DNP-TestPoint")
      (footprint "eagle-import:TH_ROUND_14MM08MM")
      (libsource (lib "eagle-import") (part "ROUND_SMDTH1.4MM"))
    )
    (comp (ref "X1")
      (value "8MHz-5x3.2mm")
      (footprint "eagle-import:7B")
      (libsource (lib "eagle-import") (part "XTAL-7B"))
    )
  )
  (nets
    (net (code "1") (name "+3.3V") (class "Default")
      (node (ref "C47") (pin "1") (pinfunction "1_1") (pintype "passive"))
      (node (ref "C48") (pin "1") (pinfunction "1_1") (pintype "passive"))
      (node (ref "C49") (pin "1") (pinfunction "1_1") (pintype "passive"))
      (node (ref "C50") (pin "1") (pinfunction "1_1") (pintype "passive"))
      (node (ref "C51") (pin "1") (pinfunction "1_1") (pintype "passive"))
      (node (ref "C52") (pin "1") (pinfunction "1_1") (pintype "passive"))
      (node (ref "C69") (pin "1") (pinfunction "1_1") (pintype "passive"))
      (node (ref "C70") (pin "1") (pinfunction "1_1") (pintype "passive"))
      (node (ref "C81") (pin "+") (pinfunction "+_+") (pintype "passive"))
      (node (ref "IC1") (pin "16") (pinfunction "VDD3_16") (pintype "input"))
      (node (ref "IC1") (pin "2") (pinfunction "VDD2_2") (pintype "input"))
      (node (ref "IC1") (pin "37") (pinfunction "VDD4_37") (pintype "input"))
      (node (ref "IC1") (pin "46") (pinfunction "VDD5_46") (pintype "input"))
      (node (ref "IC1") (pin "55") (pinfunction "VUSB3V3_55") (pintype "input"))
      (node (ref "IC1") (pin "62") (pinfunction "VDD6_62") (pintype "input"))
      (node (ref "IC1") (pin "86") (pinfunction "VDD1_86") (pintype "input"))
      (node (ref "J17") (pin "2") (pinfunction "2_2") (pintype "passive"))
      (node (ref "L13") (pin "1") (pinfunction "1_1") (pintype "passive"))
      (node (ref "R103") (pin "2") (pinfunction "2_2") (pintype "passive"))
      (node (ref "R105") (pin "2") (pinfunction "2_2") (pintype "passive"))
      (node (ref "R106") (pin "2") (pinfunction "2_2") (pintype "passive"))
      (node (ref "R129") (pin "1") (pinfunction "1_1") (pintype "passive"))
      (node (ref "R28") (pin "2") (pinfunction "2_2") (pintype "passive"))
      (node (ref "R65") (pin "1") (pinfunction "1_1") (pintype "passive"))
      (node (ref "R82") (pin "1") (pinfunction "1_1") (pintype "passive"))
      (node (ref "R91") (pin "2") (pinfunction "2_2") (pintype "passive"))
    )
    (net (code "2") (name "+3.3V{slash}1") (class "Default")
      (node (ref "C27") (pin "1") (pinfunction "1_1") (pintype "passive"))
      (node (ref "C28") (pin "1") (pinfunction "1_1") (pintype "passive"))
      (node (ref "IC11") (pin "2") (pinfunction "A1_2") (pintype "input"))
      (node (ref "IC11") (pin "8") (pinfunction "VCC_8") (pintype "input"))
      (node (ref "IC7") (pin "8") (pinfunction "VCC_8") (pintype "input"))
      (node (ref "IC9") (pin "3") (pinfunction "/WP_3") (pintype "input"))
      (node (ref "IC9") (pin "7") (pinfunction "/HOLD_7") (pintype "input"))
      (node (ref "IC9") (pin "8") (pinfunction "VCC_8") (pintype "input"))
      (node (ref "Q2") (pin "3") (pinfunction "D_3") (pintype "passive"))
      (node (ref "Q2") (pin "P2") (pinfunction "D1_P2") (pintype "passive"))
      (node (ref "R18") (pin "1") (pinfunction "1_1") (pintype "passive"))
      (node (ref "R25") (pin "2") (pinfunction "2_2") (pintype "passive"))
      (node (ref "R26") (pin "1") (pinfunction "1_1") (pintype "passive"))
      (node (ref "R27") (pin "1") (pinfunction "1_1") (pintype "passive"))
    )
    (net (code "3") (name "+3.3V{slash}2") (class "Default")
      (node (ref "C41") (pin "1") (pinfunction "1_1") (pintype "passive"))
      (node (ref "C86") (pin "+") (pinfunction "+_+") (pintype "passive"))
      (node (ref "IC12") (pin "8") (pinfunction "VCC_8") (pintype "input"))
      (node (ref "Q1") (pin "3") (pinfunction "D_3") (pintype "passive"))
      (node (ref "Q1") (pin "P2") (pinfunction "D1_P2") (pintype "passive"))
      (node (ref "R30") (pin "2") (pinfunction "2_2") (pintype "passive"))
      (node (ref "R34") (pin "1") (pinfunction "1_1") (pintype "passive"))
      (node (ref "R72") (pin "1") (pinfunction "1_1") (pintype "passive"))
      (node (ref "R73") (pin "2") (pinfunction "2_2") (pintype "passive"))
    )
    (net (code "4") (name "/A+") (class "Default")
      (node (ref "IC14") (pin "3") (pinfunction "3_3") (pintype "passive"))
      (node (ref "J3") (pin "4") (pinfunction "4_4") (pintype "passive"))
      (node (ref "J4") (pin "4") (pinfunction "4_4") (pintype "passive"))
      (node (ref "L8") (pin "2") (pinfunction "2_2") (pintype "passive"))
    )
    (net (code "5") (name "/A++") (class "Default")
      (node (ref "IC12") (pin "6") (pinfunction "A_6") (pintype "bidirectional"))
      (node (ref "L8") (pin "1") (pinfunction "1_1") (pintype "passive"))
      (node (ref "R32") (pin "2") (pinfunction "2_2") (pintype "passive"))
      (node (ref "R34") (pin "2") (pinfunction "2_2") (pintype "passive"))
    )
    (net (code "6") (name "/ACT-L-SENSE") (class "Default")
      (node (ref "R1") (pin "7") (pinfunction "2_7") (pintype "passive"))
      (node (ref "R1") (pin "8") (pinfunction "2_8") (pintype "passive"))
    )
    (net (code "7") (name "/ACT-L-SW") (class "Default")
      (node (ref "C44") (pin "1") (pinfunction "1_1") (pintype "passive"))
      (node (ref "J14") (pin "2") (pinfunction "2_2") (pintype "passive"))
      (node (ref "R1") (pin "1") (pinfunction "1_1") (pintype "passive"))
      (node (ref "R2") (pin "8") (pinfunction "2_8") (pintype "passive"))
    )
    (net (code "8") (name "/ACT-R-SENSE") (class "Default")
      (node (ref "R1") (pin "5") (pinfunction "2_5") (pintype "passive"))
      (node (ref "R1") (pin "6") (pinfunction "2_6") (pintype "passive"))
    )
    (net (code "9") (name "/ACT-R-SW") (class "Default")
      (node (ref "C3") (pin "1") (pinfunction "1_1") (pintype "passive"))
      (node (ref "J15") (pin "2") (pinfunction "2_2") (pintype "passive"))
      (node (ref "R1") (pin "3") (pinfunction "1_3") (pintype "passive"))
      (node (ref "R2") (pin "7") (pinfunction "2_7") (pintype "passive"))
    )
    (net (code "10") (name "/ACT_EN") (class "Default")
      (node (ref "R11") (pin "5") (pinfunction "2_5") (pintype "passive"))
      (node (ref "R11") (pin "6") (pinfunction "2_6") (pintype "passive"))
      (node (ref "R7") (pin "4") (pinfunction "1_4") (pintype "passive"))
    )
    (net (code "11") (name "/ACT_L+") (class "Default")
      (node (ref "IC2") (pin "31") (pinfunction "OUT1A_31") (pintype "output"))
      (node (ref "J14") (pin "1") (pinfunction "1_1") (pintype "passive"))
    )
    (net (code "12") (name "/ACT_L-") (class "Default")
      (node (ref "IC2") (pin "23") (pinfunction "OUT2A_23") (pintype "output"))
      (node (ref "J14") (pin "3") (pinfunction "3_3") (pintype "passive"))
    )
    (net (code "13") (name "/ACT_L1") (class "Default")
      (node (ref "IC2") (pin "27") (pinfunction "IN1_A_27") (pintype "input"))
      (node (ref "R10") (pin "5") (pinfunction "2_5") (pintype "passive"))
    )
    (net (code "14") (name "/ACT_L2") (class "Default")
      (node (ref "IC2") (pin "28") (pinfunction "IN2_A_28") (pintype "input"))
      (node (ref "R10") (pin "6") (pinfunction "2_6") (pintype "passive"))
    )
    (net (code "15") (name "/ACT_R+") (class "Default")
      (node (ref "IC2") (pin "9") (pinfunction "OUT1B_9") (pintype "output"))
      (node (ref "J15") (pin "1") (pinfunction "1_1") (pintype "passive"))
    )
    (net (code "16") (name "/ACT_R-") (class "Default")
      (node (ref "IC2") (pin "19") (pinfunction "OUT2B_19") (pintype "output"))
      (node (ref "J15") (pin "3") (pinfunction "3_3") (pintype "passive"))
    )
    (net (code "17") (name "/ACT_R1") (class "Default")
      (node (ref "IC2") (pin "13") (pinfunction "IN1_B_13") (pintype "input"))
      (node (ref "R10") (pin "7") (pinfunction "2_7") (pintype "passive"))
    )
    (net (code "18") (name "/ACT_R2") (class "Default")
      (node (ref "IC2") (pin "14") (pinfunction "IN2_B_14") (pintype "input"))
      (node (ref "R10") (pin "8") (pinfunction "2_8") (pintype "passive"))
    )
    (net (code "19") (name "/B-") (class "Default")
      (node (ref "IC14") (pin "2") (pinfunction "2_2") (pintype "passive"))
      (node (ref "J3") (pin "5") (pinfunction "5_5") (pintype "passive"))
      (node (ref "J4") (pin "5") (pinfunction "5_5") (pintype "passive"))
      (node (ref "L7") (pin "2") (pinfunction "2_2") (pintype "passive"))
    )
    (net (code "20") (name "/B--") (class "Default")
      (node (ref "IC12") (pin "7") (pinfunction "B_7") (pintype "bidirectional"))
      (node (ref "L7") (pin "1") (pinfunction "1_1") (pintype "passive"))
      (node (ref "R31") (pin "1") (pinfunction "1_1") (pintype "passive"))
      (node (ref "R32") (pin "1") (pinfunction "1_1") (pintype "passive"))
    )
    (net (code "21") (name "/CURR-SENSE") (class "Default")
      (node (ref "C66") (pin "1") (pinfunction "1_1") (pintype "passive"))
      (node (ref "IC1") (pin "14") (pinfunction "AN19/C2INC/RPG9/PMA2/RG9_14") (pintype "bidirectional"))
      (node (ref "O8") (pin "P$1") (pinfunction "TP_P$1") (pintype "passive"))
      (node (ref "R102") (pin "2") (pinfunction "2_2") (pintype "passive"))
      (node (ref "T39") (pin "P$1") (pinfunction "TP_P$1") (pintype "passive"))
    )
    (net (code "22") (name "/D+") (class "Default")
      (node (ref "IC1") (pin "57") (pinfunction "D+/RG2_57") (pintype "bidirectional"))
      (node (ref "IC15") (pin "3") (pinfunction "3_3") (pintype "passive"))
      (node (ref "J12") (pin "3_D+") (pinfunction "D+_3_D+") (pintype "bidirectional"))
    )
    (net (code "23") (name "/D-") (class "Default")
      (node (ref "IC1") (pin "56") (pinfunction "D-/RG3_56") (pintype "bidirectional"))
      (node (ref "IC15") (pin "2") (pinfunction "2_2") (pintype "passive"))
      (node (ref "J12") (pin "2_D-") (pinfunction "D-_2_D-") (pintype "bidirectional"))
    )
    (net (code "24") (name "/DOOR_L") (class "Default")
      (node (ref "R50") (pin "2") (pinfunction "1_2") (pintype "passive"))
      (node (ref "R50") (pin "3") (pinfunction "1_3") (pintype "passive"))
    )
    (net (code "25") (name "/DOOR_L_SW") (class "Default")
      (node (ref "C12") (pin "1") (pinfunction "1_1") (pintype "passive"))
      (node (ref "J14") (pin "4") (pinfunction "4_4") (pintype "passive"))
      (node (ref "R50") (pin "7") (pinfunction "2_7") (pintype "passive"))
      (node (ref "R6") (pin "2") (pinfunction "2_2") (pintype "passive"))
    )
    (net (code "26") (name "/DOOR_ON") (class "Default")
      (node (ref "Q3") (pin "5") (pinfunction "Q1G_5") (pintype "input"))
      (node (ref "R9") (pin "7") (pinfunction "2_7") (pintype "passive"))
    )
    (net (code "27") (name "/DOOR_R") (class "Default")
      (node (ref "R50") (pin "1") (pinfunction "1_1") (pintype "passive"))
      (node (ref "R50") (pin "4") (pinfunction "1_4") (pintype "passive"))
    )
    (net (code "28") (name "/DOOR_R_SW") (class "Default")
      (node (ref "C4") (pin "1") (pinfunction "1_1") (pintype "passive"))
      (node (ref "J15") (pin "4") (pinfunction "4_4") (pintype "passive"))
      (node (ref "R50") (pin "8") (pinfunction "2_8") (pintype "passive"))
      (node (ref "R8") (pin "2") (pinfunction "2_2") (pintype "passive"))
    )
    (net (code "29") (name "/LAN-CTL") (class "Default")
      (node (ref "IC1") (pin "84") (pinfunction "PMD15/RD7_84") (pintype "bidirectional"))
      (node (ref "IC12") (pin "2") (pinfunction "/RE_2") (pintype "input"))
      (node (ref "IC12") (pin "3") (pinfunction "DE_3") (pintype "input"))
      (node (ref "O31") (pin "P$1") (pinfunction "TP_P$1") (pintype "passive"))
      (node (ref "R71") (pin "1") (pinfunction "1_1") (pintype "passive"))
      (node (ref "T15") (pin "P$1") (pinfunction "TP_P$1") (pintype "passive"))
    )
    (net (code "30") (name "/LAN-RX") (class "Default")
      (node (ref "IC1") (pin "88") (pinfunction "RPF1/PMD10/RF1_88") (pintype "bidirectional"))
      (node (ref "IC12") (pin "1") (pinfunction "R_1") (pintype "output"))
      (node (ref "O29") (pin "P$1") (pinfunction "TP_P$1") (pintype "passive"))
      (node (ref "R72") (pin "2") (pinfunction "2_2") (pintype "passive"))
      (node (ref "T13") (pin "P$1") (pinfunction "TP_P$1") (pintype "passive"))
    )
    (net (code "31") (name "/LAN-TX") (class "Default")
      (node (ref "IC1") (pin "87") (pinfunction "RPF0/PMD11/RF0_87") (pintype "bidirectional"))
      (node (ref "IC12") (pin "4") (pinfunction "D_4") (pintype "input"))
      (node (ref "O30") (pin "P$1") (pinfunction "TP_P$1") (pintype "passive"))
      (node (ref "R73") (pin "1") (pinfunction "1_1") (pintype "passive"))
      (node (ref "T14") (pin "P$1") (pinfunction "TP_P$1") (pintype "passive"))
    )
    (net (code "32") (name "/LED-PIC") (class "Default")
      (node (ref "IC1") (pin "1") (pinfunction "RG15_1") (pintype "bidirectional"))
      (node (ref "O1") (pin "P$1") (pinfunction "TP_P$1") (pintype "passive"))
      (node (ref "R29") (pin "1") (pinfunction "1_1") (pintype "passive"))
      (node (ref "T36") (pin "P$1") (pinfunction "TP_P$1") (pintype "passive"))
      (node (ref "TP4") (pin "P$1") (pinfunction "TP_P$1") (pintype "passive"))
    )
    (net (code "33") (name "/PGC") (class "Default")
      (node (ref "IC1") (pin "24") (pinfunction "PGEC1/AN1/RPB1/CTED12/RB1_24") (pintype "bidirectional"))
      (node (ref "J17") (pin "5") (pinfunction "5_5") (pintype "passive"))
    )
    (net (code "34") (name "/PGD") (class "Default")
      (node (ref "IC1") (pin "25") (pinfunction "PGED1/AN0/RPB0/RB0_25") (pintype "bidirectional"))
      (node (ref "J17") (pin "4") (pinfunction "4_4") (pintype "passive"))
      (node (ref "R130") (pin "2") (pinfunction "2_2") (pintype "passive"))
    )
    (net (code "35") (name "/POWER-GOOD") (class "Default")
      (node (ref "IC6") (pin "4") (pinfunction "OUT_4") (pintype "output"))
      (node (ref "R130") (pin "1") (pinfunction "1_1") (pintype "passive"))
      (node (ref "T45") (pin "P$1") (pinfunction "TP_P$1") (pintype "passive"))
      (node (ref "TP2") (pin "P$1") (pinfunction "TP_P$1") (pintype "passive"))
    )
    (net (code "36") (name "/REF-EN") (class "Default")
      (node (ref "IC1") (pin "28") (pinfunction "VREF-/CVREF-/PMA7/RA9_28") (pintype "bidirectional"))
      (node (ref "R93") (pin "1") (pinfunction "1_1") (pintype "passive"))
    )
    (net (code "37") (name "/REF2,5V") (class "Default")
      (node (ref "C57") (pin "1") (pinfunction "1_1") (pintype "passive"))
      (node (ref "IC1") (pin "29") (pinfunction "VREF+/CVREF+/PMA6/RA10_29") (pintype "bidirectional"))
      (node (ref "IC13") (pin "2") (pinfunction "VOUT_2") (pintype "bidirectional"))
    )
    (net (code "38") (name "/SCL1-EEPROM") (class "Default")
      (node (ref "IC1") (pin "66") (pinfunction "SCL1/RPA14/RA14_66") (pintype "bidirectional"))
      (node (ref "IC11") (pin "6") (pinfunction "SCL_6") (pintype "input"))
      (node (ref "IC7") (pin "6") (pinfunction "SCL_6") (pintype "input"))
      (node (ref "R26") (pin "2") (pinfunction "2_2") (pintype "passive"))
    )
    (net (code "39") (name "/SCLK2-SPI") (class "Default")
      (node (ref "IC1") (pin "10") (pinfunction "AN16/C1IND/RPG6/SCK2/PMA5/RG6_10") (pintype "bidirectional"))
      (node (ref "IC9") (pin "6") (pinfunction "C_6") (pintype "input"))
    )
    (net (code "40") (name "/SD-CS") (class "Default")
      (node (ref "IC1") (pin "9") (pinfunction "RPC4/CTED7/RC4_9") (pintype "bidirectional"))
      (node (ref "O5") (pin "P$1") (pinfunction "TP_P$1") (pintype "passive"))
    )
    (net (code "41") (name "/SDA1-EEPROM") (class "Default")
      (node (ref "IC1") (pin "67") (pinfunction "SDA1/RPA15/RA15_67") (pintype "bidirectional"))
      (node (ref "IC11") (pin "5") (pinfunction "SDA_5") (pintype "bidirectional"))
      (node (ref "IC7") (pin "5") (pinfunction "SDA_5") (pintype "bidirectional"))
      (node (ref "R27") (pin "2") (pinfunction "2_2") (pintype "passive"))
    )
    (net (code "42") (name "/SDI2-MISO") (class "Default")
      (node (ref "IC1") (pin "22") (pinfunction "PGED3/AN3/C2INA/RPB3/RB3_22") (pintype "bidirectional"))
      (node (ref "IC9") (pin "2") (pinfunction "Q_2") (pintype "bidirectional"))
      (node (ref "O13") (pin "P$1") (pinfunction "TP_P$1") (pintype "passive"))
    )
    (net (code "43") (name "/SDO2-MOSI") (class "Default")
      (node (ref "IC1") (pin "20") (pinfunction "AN5/C1INA/RPB5/RB5_20") (pintype "bidirectional"))
      (node (ref "IC9") (pin "5") (pinfunction "D_5") (pintype "input"))
      (node (ref "O12") (pin "P$1") (pinfunction "TP_P$1") (pintype "passive"))
    )
    (net (code "44") (name "/VBAT-LAN") (class "Default")
      (node (ref "D3") (pin "C") (pinfunction "C_C") (pintype "passive"))
      (node (ref "J3") (pin "1") (pinfunction "1_1") (pintype "passive"))
      (node (ref "J3") (pin "3") (pinfunction "3_3") (pintype "passive"))
      (node (ref "J4") (pin "1") (pinfunction "1_1") (pintype "passive"))
      (node (ref "J4") (pin "3") (pinfunction "3_3") (pintype "passive"))
      (node (ref "L11") (pin "2") (pinfunction "2_2") (pintype "passive"))
    )
    (net (code "45") (name "/VBAT-LAN-F") (class "Default")
      (node (ref "C33") (pin "1") (pinfunction "1_1") (pintype "passive"))
      (node (ref "C34") (pin "1") (pinfunction "1_1") (pintype "passive"))
      (node (ref "D6") (pin "K") (pinfunction "K_K") (pintype "passive"))
      (node (ref "L11") (pin "1") (pinfunction "1_1") (pintype "passive"))
      (node (ref "Q5") (pin "2") (pinfunction "S_2") (pintype "passive"))
      (node (ref "Q5") (pin "5") (pinfunction "S_5") (pintype "passive"))
      (node (ref "R132") (pin "1") (pinfunction "1_1") (pintype "passive"))
      (node (ref "R36") (pin "2") (pinfunction "2_2") (pintype "passive"))
      (node (ref "R38") (pin "2") (pinfunction "2_2") (pintype "passive"))
      (node (ref "R42") (pin "1") (pinfunction "1_1") (pintype "passive"))
      (node (ref "R45") (pin "1") (pinfunction "1_1") (pintype "passive"))
      (node (ref "R94") (pin "1") (pinfunction "1_1") (pintype "passive"))
    )
    (net (code "46") (name "/VBAT-ON") (class "Default")
      (node (ref "IC1") (pin "52") (pinfunction "RPF2/RF2_52") (pintype "bidirectional"))
      (node (ref "O42") (pin "P$1") (pinfunction "TP_P$1") (pintype "passive"))
      (node (ref "Q4") (pin "2") (pinfunction "G_2") (pintype "passive"))
      (node (ref "R132") (pin "2") (pinfunction "2_2") (pintype "passive"))
      (node (ref "R41") (pin "1") (pinfunction "1_1") (pintype "passive"))
      (node (ref "T5") (pin "P$1") (pinfunction "TP_P$1") (pintype "passive"))
    )
    (net (code "47") (name "/VBAT-SENSE") (class "Default")
      (node (ref "C64") (pin "1") (pinfunction "1_1") (pintype "passive"))
      (node (ref "IC1") (pin "26") (pinfunction "PGEC2/AN6/RPB6/RB6_26") (pintype "bidirectional"))
      (node (ref "O15") (pin "P$1") (pinfunction "TP_P$1") (pintype "passive"))
      (node (ref "R100") (pin "1") (pinfunction "1_1") (pintype "passive"))
      (node (ref "T37") (pin "P$1") (pinfunction "TP_P$1") (pintype "passive"))
    )
    (net (code "48") (name "/VBATLAN-SENSE") (class "Default")
      (node (ref "C36") (pin "1") (pinfunction "1_1") (pintype "passive"))
      (node (ref "IC1") (pin "27") (pinfunction "PGED2/AN7/RPB7/CTED3/RB7_27") (pintype "bidirectional"))
      (node (ref "O16") (pin "P$1") (pinfunction "TP_P$1") (pintype "passive"))
      (node (ref "R101") (pin "1") (pinfunction "1_1") (pintype "passive"))
      (node (ref "T38") (pin "P$1") (pinfunction "TP_P$1") (pintype "passive"))
    )
    (net (code "49") (name "/VBUS") (class "Default")
      (node (ref "IC1") (pin "54") (pinfunction "VBUS_54") (pintype "input"))
      (node (ref "R128") (pin "2") (pinfunction "2_2") (pintype "passive"))
    )
    (net (code "50") (name "/VPS-ON") (class "Default")
      (node (ref "IC1") (pin "53") (pinfunction "RPF8/RF8_53") (pintype "bidirectional"))
      (node (ref "O41") (pin "P$1") (pinfunction "TP_P$1") (pintype "passive"))
      (node (ref "Q4") (pin "5") (pinfunction "G_5") (pintype "passive"))
      (node (ref "R44") (pin "1") (pinfunction "1_1") (pintype "passive"))
      (node (ref "T7") (pin "P$1") (pinfunction "TP_P$1") (pintype "passive"))
    )
    (net (code "51") (name "/VPS-PWR") (class "Default")
      (node (ref "D4") (pin "C") (pinfunction "C_C") (pintype "passive"))
      (node (ref "J3") (pin "6") (pinfunction "6_6") (pintype "passive"))
      (node (ref "J4") (pin "6") (pinfunction "6_6") (pintype "passive"))
      (node (ref "L10") (pin "2") (pinfunction "2_2") (pintype "passive"))
    )
    (net (code "52") (name "/VPS-PWR-F") (class "Default")
      (node (ref "L10") (pin "1") (pinfunction "1_1") (pintype "passive"))
      (node (ref "Q5") (pin "4") (pinfunction "D_4") (pintype "passive"))
      (node (ref "R23") (pin "2") (pinfunction "2_2") (pintype "passive"))
    )
    (net (code "53") (name "/VPS-SENSE") (class "Default")
      (node (ref "C65") (pin "1") (pinfunction "1_1") (pintype "passive"))
      (node (ref "IC1") (pin "12") (pinfunction "AN18/C2IND/RPG8/PMA3/RG8_12") (pintype "bidirectional"))
      (node (ref "O7") (pin "P$1") (pinfunction "TP_P$1") (pintype "passive"))
      (node (ref "R48") (pin "2") (pinfunction "2_2") (pintype "passive"))
      (node (ref "R49") (pin "1") (pinfunction "1_1") (pintype "passive"))
      (node (ref "T3") (pin "P$1") (pinfunction "TP_P$1") (pintype "passive"))
    )
    (net (code "54") (name "/{slash}3.3V1PWRON") (class "Default")
      (node (ref "IC1") (pin "21") (pinfunction "AN4/C1INB/USBOEN/RB4_21") (pintype "bidirectional"))
      (node (ref "O44") (pin "P$1") (pinfunction "TP_P$1") (pintype "passive"))
      (node (ref "R24") (pin "2") (pinfunction "2_2") (pintype "passive"))
      (node (ref "T32") (pin "P$1") (pinfunction "TP_P$1") (pintype "passive"))
    )
    (net (code "55") (name "/{slash}3.3V2PWRON") (class "Default")
      (node (ref "IC1") (pin "96") (pinfunction "TRD1/RG12_96") (pintype "bidirectional"))
      (node (ref "O23") (pin "P$1") (pinfunction "TP_P$1") (pintype "passive"))
      (node (ref "R75") (pin "2") (pinfunction "2_2") (pintype "passive"))
      (node (ref "T33") (pin "P$1") (pinfunction "TP_P$1") (pintype "passive"))
    )
    (net (code "56") (name "/{slash}FMEM1-CS") (class "Default")
      (node (ref "IC1") (pin "11") (pinfunction "AN17/C1INC/RPG7/PMA4/RG7_11") (pintype "bidirectional"))
      (node (ref "IC9") (pin "1") (pinfunction "/S_1") (pintype "input"))
      (node (ref "O6") (pin "P$1") (pinfunction "TP_P$1") (pintype "passive"))
      (node (ref "R25") (pin "1") (pinfunction "1_1") (pintype "passive"))
      (node (ref "T27") (pin "P$1") (pinfunction "TP_P$1") (pintype "passive"))
    )
    (net (code "57") (name "/{slash}MCLR") (class "Default")
      (node (ref "IC1") (pin "13") (pinfunction "~{MCLR}_13") (pintype "input"))
      (node (ref "J17") (pin "1") (pinfunction "1_1") (pintype "passive"))
      (node (ref "R90") (pin "2") (pinfunction "2_2") (pintype "passive"))
    )
    (net (code "58") (name "DGND") (class "Default")
      (node (ref "C22") (pin "2") (pinfunction "2_2") (pintype "passive"))
      (node (ref "C23") (pin "2") (pinfunction "2_2") (pintype "passive"))
      (node (ref "C24") (pin "1") (pinfunction "1_1") (pintype "passive"))
      (node (ref "C27") (pin "2") (pinfunction "2_2") (pintype "passive"))
      (node (ref "C28") (pin "2") (pinfunction "2_2") (pintype "passive"))
      (node (ref "C29") (pin "2") (pinfunction "2_2") (pintype "passive"))
      (node (ref "C30") (pin "2") (pinfunction "2_2") (pintype "passive"))
      (node (ref "C31") (pin "-") (pinfunction "-_-") (pintype "passive"))
      (node (ref "C35") (pin "2") (pinfunction "2_2") (pintype "passive"))
      (node (ref "C36") (pin "2") (pinfunction "2_2") (pintype "passive"))
      (node (ref "C40") (pin "2") (pinfunction "2_2") (pintype "passive"))
      (node (ref "C41") (pin "2") (pinfunction "2_2") (pintype "passive"))
      (node (ref "C47") (pin "2") (pinfunction "2_2") (pintype "passive"))
      (node (ref "C48") (pin "2") (pinfunction "2_2") (pintype "passive"))
      (node (ref "C49") (pin "2") (pinfunction "2_2") (pintype "passive"))
      (node (ref "C50") (pin "2") (pinfunction "2_2") (pintype "passive"))
      (node (ref "C51") (pin "2") (pinfunction "2_2") (pintype "passive"))
      (node (ref "C52") (pin "2") (pinfunction "2_2") (pintype "passive"))
      (node (ref "C53") (pin "2") (pinfunction "2_2") (pintype "passive"))
      (node (ref "C54") (pin "-") (pinfunction "-_-") (pintype "passive"))
      (node (ref "C55") (pin "2") (pinfunction "2_2") (pintype "passive"))
      (node (ref "C56") (pin "-") (pinfunction "-_-") (pintype "passive"))
      (node (ref "C57") (pin "2") (pinfunction "2_2") (pintype "passive"))
      (node (ref "C58") (pin "2") (pinfunction "2_2") (pintype "passive"))
      (node (ref "C59") (pin "2") (pinfunction "2_2") (pintype "passive"))
      (node (ref "C60") (pin "2") (pinfunction "2_2") (pintype "passive"))
      (node (ref "C61") (pin "2") (pinfunction "2_2") (pintype "passive"))
      (node (ref "C62") (pin "2") (pinfunction "2_2") (pintype "passive"))
      (node (ref "C63") (pin "2") (pinfunction "2_2") (pintype "passive"))
      (node (ref "C64") (pin "2") (pinfunction "2_2") (pintype "passive"))
      (node (ref "C65") (pin "2") (pinfunction "2_2") (pintype "passive"))
      (node (ref "C66") (pin "2") (pinfunction "2_2") (pintype "passive"))
      (node (ref "C67") (pin "2") (pinfunction "2_2") (pintype "passive"))
      (node (ref "C81") (pin "-") (pinfunction "-_-") (pintype "passive"))
      (node (ref "C83") (pin "2") (pinfunction "2_2") (pintype "passive"))
      (node (ref "C84") (pin "2") (pinfunction "2_2") (pintype "passive"))
      (node (ref "C85") (pin "2") (pinfunction "2_2") (pintype "passive"))
      (node (ref "C86") (pin "-") (pinfunction "-_-") (pintype "passive"))
      (node (ref "C88") (pin "2") (pinfunction "2_2") (pintype "passive"))
      (node (ref "D2") (pin "-") (pinfunction "A_-") (pintype "passive"))
      (node (ref "D5") (pin "K") (pinfunction "K_K") (pintype "passive"))
      (node (ref "D7") (pin "A") (pinfunction "A_A") (pintype "passive"))
      (node (ref "IC1") (pin "15") (pinfunction "VSS2_15") (pintype "input"))
      (node (ref "IC1") (pin "31") (pinfunction "AVSS_31") (pintype "input"))
      (node (ref "IC1") (pin "36") (pinfunction "VSS3_36") (pintype "input"))
      (node (ref "IC1") (pin "45") (pinfunction "VSS4_45") (pintype "input"))
      (node (ref "IC1") (pin "65") (pinfunction "VSS5_65") (pintype "input"))
      (node (ref "IC1") (pin "75") (pinfunction "VSS1_75") (pintype "input"))
      (node (ref "IC10") (pin "1") (pinfunction "GND_1") (pintype "input"))
      (node (ref "IC10") (pin "2") (pinfunction "GND1_2") (pintype "input"))
      (node (ref "IC11") (pin "1") (pinfunction "A0_1") (pintype "input"))
      (node (ref "IC11") (pin "3") (pinfunction "A2_3") (pintype "input"))
      (node (ref "IC11") (pin "4") (pinfunction "GND_4") (pintype "input"))
      (node (ref "IC12") (pin "5") (pinfunction "GND_5") (pintype "input"))
      (node (ref "IC13") (pin "3") (pinfunction "GND_3") (pintype "bidirectional"))
      (node (ref "IC15") (pin "1") (pinfunction "1_1") (pintype "input"))
      (node (ref "IC16") (pin "4") (pinfunction "V-_4") (pintype "input"))
      (node (ref "IC6") (pin "2") (pinfunction "GND_2") (pintype "input"))
      (node (ref "IC7") (pin "1") (pinfunction "A0_1") (pintype "input"))
      (node (ref "IC7") (pin "2") (pinfunction "A1_2") (pintype "input"))
      (node (ref "IC7") (pin "3") (pinfunction "A2_3") (pintype "input"))
      (node (ref "IC7") (pin "4") (pinfunction "GND_4") (pintype "input"))
      (node (ref "IC7") (pin "7") (pinfunction "WP_7") (pintype "input"))
      (node (ref "IC8") (pin "10") (pinfunction "SYNC_10") (pintype "bidirectional"))
      (node (ref "IC8") (pin "EP") (pinfunction "GND_EP") (pintype "bidirectional"))
      (node (ref "IC9") (pin "4") (pinfunction "GND_4") (pintype "input"))
      (node (ref "J12") (pin "4_GND") (pinfunction "GND_4_GND") (pintype "bidirectional"))
      (node (ref "J12") (pin "SH1") (pinfunction "GND_SH1_SH1") (pintype "bidirectional"))
      (node (ref "J12") (pin "SH2") (pinfunction "GND_SH2_SH2") (pintype "bidirectional"))
      (node (ref "J17") (pin "3") (pinfunction "3_3") (pintype "passive"))
      (node (ref "L12") (pin "1") (pinfunction "1_1") (pintype "passive"))
      (node (ref "L2") (pin "2") (pinfunction "2_2") (pintype "passive"))
      (node (ref "PCB1") (pin "PAD_GND_1") (pinfunction "PAD_GND_1_PAD_GND_1") (pintype "bidirectional"))
      (node (ref "PCB1") (pin "PAD_GND_2") (pinfunction "PAD_GND_2_PAD_GND_2") (pintype "bidirectional"))
      (node (ref "PCB1") (pin "PAD_GND_3") (pinfunction "PAD_GND_3_PAD_GND_3") (pintype "bidirectional"))
      (node (ref "PCB1") (pin "PAD_GND_4") (pinfunction "PAD_GND_4_PAD_GND_4") (pintype "bidirectional"))
      (node (ref "R17") (pin "2") (pinfunction "2_2") (pintype "passive"))
      (node (ref "R19") (pin "2") (pinfunction "2_2") (pintype "passive"))
      (node (ref "R21") (pin "2") (pinfunction "2_2") (pintype "passive"))
      (node (ref "R31") (pin "2") (pinfunction "2_2") (pintype "passive"))
      (node (ref "R40") (pin "1") (pinfunction "1_1") (pintype "passive"))
      (node (ref "R41") (pin "2") (pinfunction "2_2") (pintype "passive"))
      (node (ref "R43") (pin "1") (pinfunction "1_1") (pintype "passive"))
      (node (ref "R44") (pin "2") (pinfunction "2_2") (pintype "passive"))
      (node (ref "R46") (pin "1") (pinfunction "1_1") (pintype "passive"))
      (node (ref "R48") (pin "1") (pinfunction "1_1") (pintype "passive"))
      (node (ref "R71") (pin "2") (pinfunction "2_2") (pintype "passive"))
      (node (ref "R96") (pin "2") (pinfunction "2_2") (pintype "passive"))
      (node (ref "R99") (pin "2") (pinfunction "2_2") (pintype "passive"))
    )
    (net (code "59") (name "Net-(C24-Pad2)") (class "Default")
      (node (ref "C24") (pin "2") (pinfunction "2_2") (pintype "passive"))
      (node (ref "R77") (pin "2") (pinfunction "2_2") (pintype "passive"))
    )
    (net (code "60") (name "Net-(C39-Pad1)") (class "Default")
      (node (ref "C39") (pin "1") (pinfunction "1_1") (pintype "passive"))
      (node (ref "IC14") (pin "4") (pinfunction "4_4") (pintype "input"))
      (node (ref "R30") (pin "1") (pinfunction "1_1") (pintype "passive"))
    )
    (net (code "61") (name "Net-(C39-Pad2)") (class "Default")
      (node (ref "C39") (pin "2") (pinfunction "2_2") (pintype "passive"))
      (node (ref "D3") (pin "A") (pinfunction "A_A") (pintype "passive"))
      (node (ref "D4") (pin "A") (pinfunction "A_A") (pintype "passive"))
      (node (ref "IC14") (pin "1") (pinfunction "1_1") (pintype "input"))
      (node (ref "J3") (pin "2") (pinfunction "2_2") (pintype "passive"))
      (node (ref "J3") (pin "7") (pinfunction "7_7") (pintype "passive"))
      (node (ref "J3") (pin "8") (pinfunction "8_8") (pintype "passive"))
      (node (ref "J4") (pin "2") (pinfunction "2_2") (pintype "passive"))
      (node (ref "J4") (pin "7") (pinfunction "7_7") (pintype "passive"))
      (node (ref "J4") (pin "8") (pinfunction "8_8") (pintype "passive"))
      (node (ref "L12") (pin "2") (pinfunction "2_2") (pintype "passive"))
    )
    (net (code "62") (name "Net-(C40-Pad1)") (class "Default")
      (node (ref "C40") (pin "1") (pinfunction "1_1") (pintype "passive"))
      (node (ref "R90") (pin "1") (pinfunction "1_1") (pintype "passive"))
      (node (ref "R91") (pin "1") (pinfunction "1_1") (pintype "passive"))
    )
    (net (code "63") (name "Net-(D1-K)") (class "Default")
      (node (ref "C37") (pin "2") (pinfunction "2_2") (pintype "passive"))
      (node (ref "D1") (pin "2") (pinfunction "K_2") (pintype "passive"))
      (node (ref "IC2") (pin "17") (pinfunction "VBOOT_17") (pintype "input"))
    )
    (net (code "64") (name "Net-(D1-KA)") (class "Default")
      (node (ref "C2") (pin "1") (pinfunction "1_1") (pintype "passive"))
      (node (ref "D1") (pin "3") (pinfunction "KA_3") (pintype "passive"))
    )
    (net (code "65") (name "Net-(D2-C)") (class "Default")
      (node (ref "C26") (pin "1") (pinfunction "1_1") (pintype "passive"))
      (node (ref "C30") (pin "1") (pinfunction "1_1") (pintype "passive"))
      (node (ref "C31") (pin "+") (pinfunction "+_+") (pintype "passive"))
      (node (ref "D2") (pin "+") (pinfunction "C_+") (pintype "passive"))
      (node (ref "IC8") (pin "1") (pinfunction "BD_1") (pintype "bidirectional"))
      (node (ref "L9") (pin "2") (pinfunction "2_2") (pintype "passive"))
      (node (ref "R129") (pin "2") (pinfunction "2_2") (pintype "passive"))
      (node (ref "R20") (pin "1") (pinfunction "1_1") (pintype "passive"))
    )
    (net (code "66") (name "Net-(D5-PadA)") (class "Default")
      (node (ref "D5") (pin "A") (pinfunction "A_A") (pintype "passive"))
      (node (ref "R29") (pin "2") (pinfunction "2_2") (pintype "passive"))
    )
    (net (code "67") (name "Net-(D9-C)") (class "Default")
      (node (ref "D9") (pin "3") (pinfunction "C_3") (pintype "passive"))
      (node (ref "R2") (pin "1") (pinfunction "1_1") (pintype "passive"))
      (node (ref "R2") (pin "2") (pinfunction "1_2") (pintype "passive"))
      (node (ref "R7") (pin "6") (pinfunction "2_6") (pintype "passive"))
    )
    (net (code "68") (name "Net-(IC1-AVDD)") (class "Default")
      (node (ref "C55") (pin "1") (pinfunction "1_1") (pintype "passive"))
      (node (ref "C56") (pin "+") (pinfunction "+_+") (pintype "passive"))
      (node (ref "C88") (pin "1") (pinfunction "1_1") (pintype "passive"))
      (node (ref "IC1") (pin "30") (pinfunction "AVDD_30") (pintype "input"))
      (node (ref "R92") (pin "2") (pinfunction "2_2") (pintype "passive"))
    )
    (net (code "69") (name "Net-(IC1-CLKI{slash}RC12{slash}OSC1)") (class "Default")
      (node (ref "C60") (pin "1") (pinfunction "1_1") (pintype "passive"))
      (node (ref "IC1") (pin "63") (pinfunction "CLKI/RC12/OSC1_63") (pintype "bidirectional"))
      (node (ref "X1") (pin "3") (pinfunction "2_3") (pintype "passive"))
    )
    (net (code "70") (name "Net-(IC1-CLKO{slash}RC15{slash}OSC2)") (class "Default")
      (node (ref "C61") (pin "1") (pinfunction "1_1") (pintype "passive"))
      (node (ref "IC1") (pin "64") (pinfunction "CLKO/RC15/OSC2_64") (pintype "bidirectional"))
      (node (ref "X1") (pin "1") (pinfunction "1_1") (pintype "passive"))
    )
    (net (code "71") (name "Net-(IC1-VCAP)") (class "Default")
      (node (ref "C53") (pin "1") (pinfunction "1_1") (pintype "passive"))
      (node (ref "C54") (pin "+") (pinfunction "+_+") (pintype "passive"))
      (node (ref "IC1") (pin "85") (pinfunction "VCAP_85") (pintype "input"))
    )
    (net (code "72") (name "Net-(IC2-EN_A)") (class "Default")
      (node (ref "C5") (pin "1") (pinfunction "1_1") (pintype "passive"))
      (node (ref "IC2") (pin "25") (pinfunction "EN_A_25") (pintype "input"))
      (node (ref "R11") (pin "4") (pinfunction "1_4") (pintype "passive"))
    )
    (net (code "73") (name "Net-(IC2-EN_B)") (class "Default")
      (node (ref "C43") (pin "1") (pinfunction "1_1") (pintype "passive"))
      (node (ref "IC2") (pin "16") (pinfunction "EN_B_16") (pintype "input"))
      (node (ref "R11") (pin "3") (pinfunction "1_3") (pintype "passive"))
    )
    (net (code "74") (name "Net-(IC2-RCA)") (class "Default")
      (node (ref "C7") (pin "1") (pinfunction "1_1") (pintype "passive"))
      (node (ref "IC2") (pin "30") (pinfunction "RCA_30") (pintype "input"))
      (node (ref "R11") (pin "2") (pinfunction "1_2") (pintype "passive"))
    )
    (net (code "75") (name "Net-(IC2-RCB)") (class "Default")
      (node (ref "C6") (pin "1") (pinfunction "1_1") (pintype "passive"))
      (node (ref "IC2") (pin "11") (pinfunction "RCB_11") (pintype "input"))
      (node (ref "R11") (pin "1") (pinfunction "1_1") (pintype "passive"))
    )
    (net (code "76") (name "Net-(IC2-SENSE_A)") (class "Default")
      (node (ref "IC2") (pin "29") (pinfunction "SENSE_A_29") (pintype "input"))
      (node (ref "R5") (pin "2") (pinfunction "2_2") (pintype "passive"))
    )
    (net (code "77") (name "Net-(IC2-SENSE_B)") (class "Default")
      (node (ref "IC2") (pin "12") (pinfunction "SENSE_B_12") (pintype "input"))
      (node (ref "R4") (pin "2") (pinfunction "2_2") (pintype "passive"))
    )
    (net (code "78") (name "Net-(IC2-VCP)") (class "Default")
      (node (ref "C2") (pin "2") (pinfunction "2_2") (pintype "passive"))
      (node (ref "IC2") (pin "24") (pinfunction "VCP_24") (pintype "input"))
    )
    (net (code "79") (name "Net-(IC2-VREF_A)") (class "Default")
      (node (ref "IC2") (pin "15") (pinfunction "VREF_B_15") (pintype "input"))
      (node (ref "IC2") (pin "26") (pinfunction "VREF_A_26") (pintype "input"))
      (node (ref "R3") (pin "2") (pinfunction "2_2") (pintype "passive"))
      (node (ref "R7") (pin "5") (pinfunction "2_5") (pintype "passive"))
    )
    (net (code "80") (name "Net-(IC6-HTH)") (class "Default")
      (node (ref "IC6") (pin "1") (pinfunction "HTH_1") (pintype "input"))
      (node (ref "R46") (pin "2") (pinfunction "2_2") (pintype "passive"))
      (node (ref "R47") (pin "1") (pinfunction "1_1") (pintype "passive"))
    )
    (net (code "81") (name "Net-(IC6-LTH)") (class "Default")
      (node (ref "IC6") (pin "3") (pinfunction "LTH_3") (pintype "input"))
      (node (ref "R33") (pin "1") (pinfunction "1_1") (pintype "passive"))
      (node (ref "R47") (pin "2") (pinfunction "2_2") (pintype "passive"))
    )
    (net (code "82") (name "Net-(IC6-VDD)") (class "Default")
      (node (ref "C35") (pin "1") (pinfunction "1_1") (pintype "passive"))
      (node (ref "IC6") (pin "5") (pinfunction "VDD_5") (pintype "input"))
      (node (ref "R28") (pin "1") (pinfunction "1_1") (pintype "passive"))
    )
    (net (code "83") (name "Net-(IC8-BOOST)") (class "Default")
      (node (ref "C25") (pin "2") (pinfunction "2_2") (pintype "passive"))
      (node (ref "IC8") (pin "2") (pinfunction "BOOST_2") (pintype "bidirectional"))
    )
    (net (code "84") (name "Net-(IC8-EN)") (class "Default")
      (node (ref "IC8") (pin "5") (pinfunction "EN_5") (pintype "bidirectional"))
      (node (ref "JP1") (pin "2") (pinfunction "2_2") (pintype "bidirectional"))
      (node (ref "R22") (pin "2") (pinfunction "2_2") (pintype "passive"))
    )
    (net (code "85") (name "Net-(IC8-FB)") (class "Default")
      (node (ref "C26") (pin "2") (pinfunction "2_2") (pintype "passive"))
      (node (ref "IC8") (pin "6") (pinfunction "FB_6") (pintype "bidirectional"))
      (node (ref "R19") (pin "1") (pinfunction "1_1") (pintype "passive"))
      (node (ref "R20") (pin "2") (pinfunction "2_2") (pintype "passive"))
    )
    (net (code "86") (name "Net-(IC8-RT)") (class "Default")
      (node (ref "IC8") (pin "8") (pinfunction "RT_8") (pintype "bidirectional"))
      (node (ref "R17") (pin "1") (pinfunction "1_1") (pintype "passive"))
    )
    (net (code "87") (name "Net-(IC8-SS)") (class "Default")
      (node (ref "IC8") (pin "7") (pinfunction "SS_7") (pintype "bidirectional"))
      (node (ref "R77") (pin "1") (pinfunction "1_1") (pintype "passive"))
    )
    (net (code "88") (name "Net-(IC8-SW)") (class "Default")
      (node (ref "C25") (pin "1") (pinfunction "1_1") (pintype "passive"))
      (node (ref "D7") (pin "K") (pinfunction "K_K") (pintype "passive"))
      (node (ref "IC8") (pin "3") (pinfunction "SW_3") (pintype "bidirectional"))
      (node (ref "L9") (pin "1") (pinfunction "1_1") (pintype "passive"))
    )
    (net (code "89") (name "Net-(IC10-OUT)") (class "Default")
      (node (ref "IC10") (pin "3") (pinfunction "OUT_3") (pintype "output"))
      (node (ref "R102") (pin "1") (pinfunction "1_1") (pintype "passive"))
    )
    (net (code "90") (name "Net-(IC10-VIN+)") (class "Default")
      (node (ref "C29") (pin "1") (pinfunction "1_1") (pintype "passive"))
      (node (ref "F1") (pin "1") (pinfunction "1_1") (pintype "passive"))
      (node (ref "IC10") (pin "5") (pinfunction "VIN+_5") (pintype "input"))
      (node (ref "R39") (pin "2") (pinfunction "2_2") (pintype "passive"))
    )
    (net (code "91") (name "Net-(IC11-WP)") (class "Default")
      (node (ref "IC11") (pin "7") (pinfunction "WP_7") (pintype "input"))
      (node (ref "R18") (pin "2") (pinfunction "2_2") (pintype "passive"))
      (node (ref "TP1") (pin "P$1") (pinfunction "TP_P$1") (pintype "passive"))
    )
    (net (code "92") (name "Net-(IC13-VIN)") (class "Default")
      (node (ref "C58") (pin "1") (pinfunction "1_1") (pintype "passive"))
      (node (ref "C59") (pin "1") (pinfunction "1_1") (pintype "passive"))
      (node (ref "IC13") (pin "1") (pinfunction "VIN_1") (pintype "bidirectional"))
      (node (ref "R93") (pin "2") (pinfunction "2_2") (pintype "passive"))
    )
    (net (code "93") (name "Net-(IC16A-+IN)") (class "Default")
      (node (ref "C62") (pin "1") (pinfunction "1_1") (pintype "passive"))
      (node (ref "IC16") (pin "3") (pinfunction "+IN_3") (pintype "input"))
      (node (ref "R95") (pin "2") (pinfunction "2_2") (pintype "passive"))
      (node (ref "R96") (pin "1") (pinfunction "1_1") (pintype "passive"))
    )
    (net (code "94") (name "Net-(IC16A--IN)") (class "Default")
      (node (ref "IC16") (pin "1") (pinfunction "OUT_1") (pintype "output"))
      (node (ref "IC16") (pin "2") (pinfunction "-IN_2") (pintype "input"))
      (node (ref "R101") (pin "2") (pinfunction "2_2") (pintype "passive"))
    )
    (net (code "95") (name "Net-(IC16B-+IN)") (class "Default")
      (node (ref "C63") (pin "1") (pinfunction "1_1") (pintype "passive"))
      (node (ref "IC16") (pin "5") (pinfunction "+IN_5") (pintype "input"))
      (node (ref "R98") (pin "2") (pinfunction "2_2") (pintype "passive"))
      (node (ref "R99") (pin "1") (pinfunction "1_1") (pintype "passive"))
    )
    (net (code "96") (name "Net-(IC16B--IN)") (class "Default")
      (node (ref "IC16") (pin "6") (pinfunction "-IN_6") (pintype "input"))
      (node (ref "IC16") (pin "7") (pinfunction "OUT_7") (pintype "output"))
      (node (ref "R100") (pin "2") (pinfunction "2_2") (pintype "passive"))
    )
    (net (code "97") (name "Net-(IC16C-V+)") (class "Default")
      (node (ref "C67") (pin "1") (pinfunction "1_1") (pintype "passive"))
      (node (ref "IC16") (pin "8") (pinfunction "V+_8") (pintype "input"))
      (node (ref "R103") (pin "1") (pinfunction "1_1") (pintype "passive"))
    )
    (net (code "98") (name "Net-(J12-+5V)") (class "Default")
      (node (ref "C85") (pin "1") (pinfunction "1_1") (pintype "passive"))
      (node (ref "D6") (pin "A") (pinfunction "A_A") (pintype "passive"))
      (node (ref "IC15") (pin "4") (pinfunction "4_4") (pintype "input"))
      (node (ref "J12") (pin "1_+5V") (pinfunction "+5V_1_+5V") (pintype "bidirectional"))
      (node (ref "R128") (pin "1") (pinfunction "1_1") (pintype "passive"))
    )
    (net (code "99") (name "Net-(JP1-Pad1)") (class "Default")
      (node (ref "JP1") (pin "1") (pinfunction "1_1") (pintype "bidirectional"))
      (node (ref "R21") (pin "1") (pinfunction "1_1") (pintype "passive"))
    )
    (net (code "100") (name "Net-(L13-Pad2)") (class "Default")
      (node (ref "L13") (pin "2") (pinfunction "2_2") (pintype "passive"))
      (node (ref "R92") (pin "1") (pinfunction "1_1") (pintype "passive"))
    )
    (net (code "101") (name "Net-(Q1B-G)") (class "Default")
      (node (ref "C70") (pin "2") (pinfunction "2_2") (pintype "passive"))
      (node (ref "Q1") (pin "5") (pinfunction "G_5") (pintype "passive"))
      (node (ref "R75") (pin "1") (pinfunction "1_1") (pintype "passive"))
      (node (ref "R82") (pin "2") (pinfunction "2_2") (pintype "passive"))
    )
    (net (code "102") (name "Net-(Q1B-S)") (class "Default")
      (node (ref "Q1") (pin "4") (pinfunction "S_4") (pintype "passive"))
      (node (ref "R106") (pin "1") (pinfunction "1_1") (pintype "passive"))
    )
    (net (code "103") (name "Net-(Q2B-G)") (class "Default")
      (node (ref "C69") (pin "2") (pinfunction "2_2") (pintype "passive"))
      (node (ref "Q2") (pin "5") (pinfunction "G_5") (pintype "passive"))
      (node (ref "R24") (pin "1") (pinfunction "1_1") (pintype "passive"))
      (node (ref "R65") (pin "2") (pinfunction "2_2") (pintype "passive"))
    )
    (net (code "104") (name "Net-(Q2B-S)") (class "Default")
      (node (ref "Q2") (pin "4") (pinfunction "S_4") (pintype "passive"))
      (node (ref "R105") (pin "1") (pinfunction "1_1") (pintype "passive"))
    )
    (net (code "105") (name "Net-(Q3-Q2D1)") (class "Default")
      (node (ref "Q3") (pin "2") (pinfunction "Q2D1_2") (pintype "bidirectional"))
      (node (ref "Q3") (pin "3") (pinfunction "Q2D2_3") (pintype "bidirectional"))
      (node (ref "R6") (pin "1") (pinfunction "1_1") (pintype "passive"))
      (node (ref "R8") (pin "1") (pinfunction "1_1") (pintype "passive"))
    )
    (net (code "106") (name "Net-(Q3-Q2G)") (class "Default")
      (node (ref "Q3") (pin "6") (pinfunction "Q2G_6") (pintype "input"))
      (node (ref "R9") (pin "3") (pinfunction "1_3") (pintype "passive"))
    )
    (net (code "107") (name "Net-(Q4A-D)") (class "Default")
      (node (ref "C33") (pin "2") (pinfunction "2_2") (pintype "passive"))
      (node (ref "Q4") (pin "6") (pinfunction "D_6") (pintype "passive"))
      (node (ref "Q5") (pin "1") (pinfunction "G_1") (pintype "passive"))
      (node (ref "R42") (pin "2") (pinfunction "2_2") (pintype "passive"))
    )
    (net (code "108") (name "Net-(Q4A-S)") (class "Default")
      (node (ref "Q4") (pin "1") (pinfunction "S_1") (pintype "passive"))
      (node (ref "R40") (pin "2") (pinfunction "2_2") (pintype "passive"))
    )
    (net (code "109") (name "Net-(Q4B-D)") (class "Default")
      (node (ref "C34") (pin "2") (pinfunction "2_2") (pintype "passive"))
      (node (ref "Q4") (pin "3") (pinfunction "D_3") (pintype "passive"))
      (node (ref "Q5") (pin "3") (pinfunction "G_3") (pintype "passive"))
      (node (ref "R45") (pin "2") (pinfunction "2_2") (pintype "passive"))
    )
    (net (code "110") (name "Net-(Q4B-S)") (class "Default")
      (node (ref "Q4") (pin "4") (pinfunction "S_4") (pintype "passive"))
      (node (ref "R43") (pin "2") (pinfunction "2_2") (pintype "passive"))
    )
    (net (code "111") (name "Net-(Q5A-D)") (class "Default")
      (node (ref "F1") (pin "2") (pinfunction "2_2") (pintype "passive"))
      (node (ref "Q5") (pin "6") (pinfunction "D_6") (pintype "passive"))
      (node (ref "R35") (pin "1") (pinfunction "1_1") (pintype "passive"))
      (node (ref "R37") (pin "1") (pinfunction "1_1") (pintype "passive"))
      (node (ref "R97") (pin "1") (pinfunction "1_1") (pintype "passive"))
    )
    (net (code "112") (name "Net-(R23-Pad1)") (class "Default")
      (node (ref "R23") (pin "1") (pinfunction "1_1") (pintype "passive"))
      (node (ref "R49") (pin "2") (pinfunction "2_2") (pintype "passive"))
    )
    (net (code "113") (name "Net-(R35-Pad2)") (class "Default")
      (node (ref "R35") (pin "2") (pinfunction "2_2") (pintype "passive"))
      (node (ref "R36") (pin "1") (pinfunction "1_1") (pintype "passive"))
      (node (ref "R37") (pin "2") (pinfunction "2_2") (pintype "passive"))
      (node (ref "R38") (pin "1") (pinfunction "1_1") (pintype "passive"))
    )
    (net (code "114") (name "Net-(R94-Pad2)") (class "Default")
      (node (ref "R94") (pin "2") (pinfunction "2_2") (pintype "passive"))
      (node (ref "R95") (pin "1") (pinfunction "1_1") (pintype "passive"))
    )
    (net (code "115") (name "Net-(R97-Pad2)") (class "Default")
      (node (ref "R97") (pin "2") (pinfunction "2_2") (pintype "passive"))
      (node (ref "R98") (pin "1") (pinfunction "1_1") (pintype "passive"))
    )
    (net (code "116") (name "PGND") (class "Default")
      (node (ref "C1") (pin "2") (pinfunction "2_2") (pintype "passive"))
      (node (ref "C12") (pin "2") (pinfunction "2_2") (pintype "passive"))
      (node (ref "C3") (pin "2") (pinfunction "2_2") (pintype "passive"))
      (node (ref "C38") (pin "2") (pinfunction "2_2") (pintype "passive"))
      (node (ref "C4") (pin "2") (pinfunction "2_2") (pintype "passive"))
      (node (ref "C43") (pin "2") (pinfunction "2_2") (pintype "passive"))
      (node (ref "C44") (pin "2") (pinfunction "2_2") (pintype "passive"))
      (node (ref "C5") (pin "2") (pinfunction "2_2") (pintype "passive"))
      (node (ref "C6") (pin "2") (pinfunction "2_2") (pintype "passive"))
      (node (ref "C7") (pin "2") (pinfunction "2_2") (pintype "passive"))
      (node (ref "D8") (pin "A") (pinfunction "A_A") (pintype "passive"))
      (node (ref "D9") (pin "1") (pinfunction "A_1") (pintype "passive"))
      (node (ref "IC2") (pin "1") (pinfunction "GND1_1") (pintype "input"))
      (node (ref "IC2") (pin "2") (pinfunction "GND2_2") (pintype "input"))
      (node (ref "IC2") (pin "21") (pinfunction "GND21_21") (pintype "input"))
      (node (ref "IC2") (pin "3") (pinfunction "GND3_3") (pintype "input"))
      (node (ref "IC2") (pin "4") (pinfunction "GND4_4") (pintype "input"))
      (node (ref "IC2") (pin "5") (pinfunction "GND5_5") (pintype "input"))
      (node (ref "IC2") (pin "6") (pinfunction "GND6_6") (pintype "input"))
      (node (ref "IC2") (pin "7") (pinfunction "GND7_7") (pintype "input"))
      (node (ref "IC2") (pin "8") (pinfunction "GND8_8") (pintype "input"))
      (node (ref "IC2") (pin "G") (pinfunction "GNEXP_G") (pintype "input"))
      (node (ref "J14") (pin "5") (pinfunction "5_5") (pintype "passive"))
      (node (ref "J15") (pin "5") (pinfunction "5_5") (pintype "passive"))
      (node (ref "L2") (pin "1") (pinfunction "1_1") (pintype "passive"))
      (node (ref "Q3") (pin "1") (pinfunction "Q1S_1") (pintype "bidirectional"))
      (node (ref "R1") (pin "2") (pinfunction "1_2") (pintype "passive"))
      (node (ref "R1") (pin "4") (pinfunction "1_4") (pintype "passive"))
      (node (ref "R10") (pin "1") (pinfunction "1_1") (pintype "passive"))
      (node (ref "R10") (pin "2") (pinfunction "1_2") (pintype "passive"))
      (node (ref "R10") (pin "3") (pinfunction "1_3") (pintype "passive"))
      (node (ref "R10") (pin "4") (pinfunction "1_4") (pintype "passive"))
      (node (ref "R11") (pin "7") (pinfunction "2_7") (pintype "passive"))
      (node (ref "R11") (pin "8") (pinfunction "2_8") (pintype "passive"))
      (node (ref "R3") (pin "1") (pinfunction "1_1") (pintype "passive"))
      (node (ref "R4") (pin "1") (pinfunction "1_1") (pintype "passive"))
      (node (ref "R5") (pin "1") (pinfunction "1_1") (pintype "passive"))
      (node (ref "R50") (pin "5") (pinfunction "2_5") (pintype "passive"))
      (node (ref "R50") (pin "6") (pinfunction "2_6") (pintype "passive"))
      (node (ref "R9") (pin "2") (pinfunction "1_2") (pintype "passive"))
    )
    (net (code "117") (name "VACT") (class "Default")
      (node (ref "C1") (pin "1") (pinfunction "1_1") (pintype "passive"))
      (node (ref "C37") (pin "1") (pinfunction "1_1") (pintype "passive"))
      (node (ref "C38") (pin "1") (pinfunction "1_1") (pintype "passive"))
      (node (ref "D1") (pin "1") (pinfunction "A_1") (pintype "passive"))
      (node (ref "D8") (pin "C") (pinfunction "C_C") (pintype "passive"))
      (node (ref "IC2") (pin "20") (pinfunction "VS_B_20") (pintype "input"))
      (node (ref "IC2") (pin "22") (pinfunction "VS_A_22") (pintype "input"))
      (node (ref "R7") (pin "3") (pinfunction "1_3") (pintype "passive"))
    )
    (net (code "118") (name "VBAT") (class "Default")
      (node (ref "C22") (pin "1") (pinfunction "1_1") (pintype "passive"))
      (node (ref "C23") (pin "1") (pinfunction "1_1") (pintype "passive"))
      (node (ref "C83") (pin "1") (pinfunction "1_1") (pintype "passive"))
      (node (ref "C84") (pin "1") (pinfunction "1_1") (pintype "passive"))
      (node (ref "IC10") (pin "4") (pinfunction "VIN-_4") (pintype "input"))
      (node (ref "IC8") (pin "4") (pinfunction "VIN_4") (pintype "bidirectional"))
      (node (ref "JP1") (pin "3") (pinfunction "3_3") (pintype "bidirectional"))
      (node (ref "Q3") (pin "4") (pinfunction "Q2S_4") (pintype "bidirectional"))
      (node (ref "R22") (pin "1") (pinfunction "1_1") (pintype "passive"))
      (node (ref "R33") (pin "2") (pinfunction "2_2") (pintype "passive"))
      (node (ref "R39") (pin "1") (pinfunction "1_1") (pintype "passive"))
      (node (ref "R9") (pin "6") (pinfunction "2_6") (pintype "passive"))
    )
    (net (code "119") (name "unconnected-(IC1-AN8{slash}RPB8{slash}CTED10{slash}RB8-Pad32)") (class "Default")
      (node (ref "IC1") (pin "32") (pinfunction "AN8/RPB8/CTED10/RB8_32") (pintype "bidirectional"))
    )
    (net (code "120") (name "unconnected-(IC1-AN9{slash}RPB9{slash}CTED4{slash}RB9-Pad33)") (class "Default")
      (node (ref "IC1") (pin "33") (pinfunction "AN9/RPB9/CTED4/RB9_33") (pintype "bidirectional"))
    )
    (net (code "121") (name "unconnected-(IC1-AN11{slash}PMA12{slash}RB11-Pad35)") (class "Default")
      (node (ref "IC1") (pin "35") (pinfunction "AN11/PMA12/RB11_35") (pintype "bidirectional"))
    )
    (net (code "122") (name "unconnected-(IC1-AN12{slash}PMA11{slash}RB12-Pad41)") (class "Default")
      (node (ref "IC1") (pin "41") (pinfunction "AN12/PMA11/RB12_41") (pintype "bidirectional"))
    )
    (net (code "123") (name "unconnected-(IC1-AN13{slash}RB13-Pad42)") (class "Default")
      (node (ref "IC1") (pin "42") (pinfunction "AN13/RB13_42") (pintype "bidirectional"))
    )
    (net (code "124") (name "unconnected-(IC1-AN14{slash}RPB14{slash}PMA1{slash}CTED5{slash}RB14-Pad43)") (class "Default")
      (node (ref "IC1") (pin "43") (pinfunction "AN14/RPB14/PMA1/CTED5/RB14_43") (pintype "bidirectional"))
    )
    (net (code "125") (name "unconnected-(IC1-AN15{slash}RPB15{slash}PMA0{slash}CTED6{slash}{slash}RB15-Pad44)") (class "Default")
      (node (ref "IC1") (pin "44") (pinfunction "AN15/RPB15/PMA0/CTED6//RB15_44") (pintype "bidirectional"))
    )
    (net (code "126") (name "unconnected-(IC1-AN20{slash}PMD2{slash}RE2-Pad98)") (class "Default")
      (node (ref "IC1") (pin "98") (pinfunction "AN20/PMD2/RE2_98") (pintype "bidirectional"))
    )
    (net (code "127") (name "unconnected-(IC1-AN21{slash}PMD4{slash}RE4-Pad100)") (class "Default")
      (node (ref "IC1") (pin "100") (pinfunction "AN21/PMD4/RE4_100") (pintype "bidirectional"))
    )
    (net (code "128") (name "unconnected-(IC1-AN22{slash}RPE5{slash}PMD5{slash}RE5-Pad3)") (class "Default")
      (node (ref "IC1") (pin "3") (pinfunction "AN22/RPE5/PMD5/RE5_3") (pintype "bidirectional"))
    )
    (net (code "129") (name "unconnected-(IC1-AN23{slash}PMD6{slash}RE6-Pad4)") (class "Default")
      (node (ref "IC1") (pin "4") (pinfunction "AN23/PMD6/RE6_4") (pintype "bidirectional"))
    )
    (net (code "130") (name "unconnected-(IC1-AN24{slash}RPD1{slash}RD1-Pad76)") (class "Default")
      (node (ref "IC1") (pin "76") (pinfunction "AN24/RPD1/RD1_76") (pintype "bidirectional"))
    )
    (net (code "131") (name "unconnected-(IC1-AN25{slash}RPD2{slash}RD2-Pad77)") (class "Default")
      (node (ref "IC1") (pin "77") (pinfunction "AN25/RPD2/RD2_77") (pintype "bidirectional"))
    )
    (net (code "132") (name "unconnected-(IC1-AN26{slash}RPD3{slash}RD3-Pad78)") (class "Default")
      (node (ref "IC1") (pin "78") (pinfunction "AN26/RPD3/RD3_78") (pintype "bidirectional"))
    )
    (net (code "133") (name "unconnected-(IC1-AN27{slash}PMD7{slash}RE7-Pad5)") (class "Default")
      (node (ref "IC1") (pin "5") (pinfunction "AN27/PMD7/RE7_5") (pintype "bidirectional"))
    )
    (net (code "134") (name "unconnected-(IC1-CVREFOUT{slash}AN10{slash}RPB10{slash}PMA13{slash}CTED11{slash}RB10-Pad34)") (class "Default")
      (node (ref "IC1") (pin "34") (pinfunction "CVREFOUT/AN10/RPB10/PMA13/CTED11/RB10_34") (pintype "bidirectional"))
    )
    (net (code "135") (name "unconnected-(IC1-PGEC3{slash}AN2{slash}C2INB{slash}RPB2{slash}CTED13{slash}RB2-Pad23)") (class "Default")
      (node (ref "IC1") (pin "23") (pinfunction "PGEC3/AN2/C2INB/RPB2/CTED13/RB2_23") (pintype "bidirectional"))
    )
    (net (code "136") (name "unconnected-(IC1-PMD0{slash}RE0-Pad93)") (class "Default")
      (node (ref "IC1") (pin "93") (pinfunction "PMD0/RE0_93") (pintype "bidirectional"))
    )
    (net (code "137") (name "unconnected-(IC1-PMD1{slash}RE1-Pad94)") (class "Default")
      (node (ref "IC1") (pin "94") (pinfunction "PMD1/RE1_94") (pintype "bidirectional"))
    )
    (net (code "138") (name "unconnected-(IC1-PMD13{slash}RD13-Pad80)") (class "Default")
      (node (ref "IC1") (pin "80") (pinfunction "PMD13/RD13_80") (pintype "bidirectional"))
    )
    (net (code "139") (name "unconnected-(IC1-PMD14{slash}RD6-Pad83)") (class "Default")
      (node (ref "IC1") (pin "83") (pinfunction "PMD14/RD6_83") (pintype "bidirectional"))
    )
    (net (code "140") (name "unconnected-(IC1-RPC1{slash}RC1-Pad6)") (class "Default")
      (node (ref "IC1") (pin "6") (pinfunction "RPC1/RC1_6") (pintype "bidirectional"))
    )
    (net (code "141") (name "unconnected-(IC1-RPC2{slash}RC2-Pad7)") (class "Default")
      (node (ref "IC1") (pin "7") (pinfunction "RPC2/RC2_7") (pintype "bidirectional"))
    )
    (net (code "142") (name "unconnected-(IC1-RPC3{slash}RC3-Pad8)") (class "Default")
      (node (ref "IC1") (pin "8") (pinfunction "RPC3/RC3_8") (pintype "bidirectional"))
    )
    (net (code "143") (name "unconnected-(IC1-RPD0{slash}INT0{slash}RD0-Pad72)") (class "Default")
      (node (ref "IC1") (pin "72") (pinfunction "RPD0/INT0/RD0_72") (pintype "bidirectional"))
    )
    (net (code "144") (name "unconnected-(IC1-RPD4{slash}PMWR{slash}RD4-Pad81)") (class "Default")
      (node (ref "IC1") (pin "81") (pinfunction "RPD4/PMWR/RD4_81") (pintype "bidirectional"))
    )
    (net (code "145") (name "unconnected-(IC1-RPD5{slash}PMRD{slash}RD5-Pad82)") (class "Default")
      (node (ref "IC1") (pin "82") (pinfunction "RPD5/PMRD/RD5_82") (pintype "bidirectional"))
    )
    (net (code "146") (name "unconnected-(IC1-RPD8{slash}RTCC{slash}RD8-Pad68)") (class "Default")
      (node (ref "IC1") (pin "68") (pinfunction "RPD8/RTCC/RD8_68") (pintype "bidirectional"))
    )
    (net (code "147") (name "unconnected-(IC1-RPD9{slash}RD9-Pad69)") (class "Default")
      (node (ref "IC1") (pin "69") (pinfunction "RPD9/RD9_69") (pintype "bidirectional"))
    )
    (net (code "148") (name "unconnected-(IC1-RPD10{slash}SCK1{slash}PMCS2{slash}RD10-Pad70)") (class "Default")
      (node (ref "IC1") (pin "70") (pinfunction "RPD10/SCK1/PMCS2/RD10_70") (pintype "bidirectional"))
    )
    (net (code "149") (name "unconnected-(IC1-RPD11{slash}PMCS1{slash}RD11-Pad71)") (class "Default")
      (node (ref "IC1") (pin "71") (pinfunction "RPD11/PMCS1/RD11_71") (pintype "bidirectional"))
    )
    (net (code "150") (name "unconnected-(IC1-RPD12{slash}PMD12{slash}RD12-Pad79)") (class "Default")
      (node (ref "IC1") (pin "79") (pinfunction "RPD12/PMD12/RD12_79") (pintype "bidirectional"))
    )
    (net (code "151") (name "unconnected-(IC1-RPD14{slash}RD14-Pad47)") (class "Default")
      (node (ref "IC1") (pin "47") (pinfunction "RPD14/RD14_47") (pintype "bidirectional"))
    )
    (net (code "152") (name "unconnected-(IC1-RPD15{slash}RD15-Pad48)") (class "Default")
      (node (ref "IC1") (pin "48") (pinfunction "RPD15/RD15_48") (pintype "bidirectional"))
    )
    (net (code "153") (name "unconnected-(IC1-RPE3{slash}PMD3{slash}RE3-Pad99)") (class "Default")
      (node (ref "IC1") (pin "99") (pinfunction "RPE3/PMD3/RE3_99") (pintype "bidirectional"))
    )
    (net (code "154") (name "unconnected-(IC1-RPE8{slash}RE8-Pad18)") (class "Default")
      (node (ref "IC1") (pin "18") (pinfunction "RPE8/RE8_18") (pintype "bidirectional"))
    )
    (net (code "155") (name "unconnected-(IC1-RPE9{slash}RE9-Pad19)") (class "Default")
      (node (ref "IC1") (pin "19") (pinfunction "RPE9/RE9_19") (pintype "bidirectional"))
    )
    (net (code "156") (name "unconnected-(IC1-RPF3{slash}USBID{slash}RF3-Pad51)") (class "Default")
      (node (ref "IC1") (pin "51") (pinfunction "RPF3/USBID/RF3_51") (pintype "bidirectional"))
    )
    (net (code "157") (name "unconnected-(IC1-RPF4{slash}PMA9{slash}RF4-Pad49)") (class "Default")
      (node (ref "IC1") (pin "49") (pinfunction "RPF4/PMA9/RF4_49") (pintype "bidirectional"))
    )
    (net (code "158") (name "unconnected-(IC1-RPF5{slash}PMA8{slash}RF5-Pad50)") (class "Default")
      (node (ref "IC1") (pin "50") (pinfunction "RPF5/PMA8/RF5_50") (pintype "bidirectional"))
    )
    (net (code "159") (name "unconnected-(IC1-RPF12{slash}RF12-Pad40)") (class "Default")
      (node (ref "IC1") (pin "40") (pinfunction "RPF12/RF12_40") (pintype "bidirectional"))
    )
    (net (code "160") (name "unconnected-(IC1-RPF13{slash}RF13-Pad39)") (class "Default")
      (node (ref "IC1") (pin "39") (pinfunction "RPF13/RF13_39") (pintype "bidirectional"))
    )
    (net (code "161") (name "unconnected-(IC1-RPG0{slash}PMD8{slash}RG0-Pad90)") (class "Default")
      (node (ref "IC1") (pin "90") (pinfunction "RPG0/PMD8/RG0_90") (pintype "bidirectional"))
    )
    (net (code "162") (name "unconnected-(IC1-RPG1{slash}PMD9{slash}RG1-Pad89)") (class "Default")
      (node (ref "IC1") (pin "89") (pinfunction "RPG1/PMD9/RG1_89") (pintype "bidirectional"))
    )
    (net (code "163") (name "unconnected-(IC1-SCL2{slash}RA2-Pad58)") (class "Default")
      (node (ref "IC1") (pin "58") (pinfunction "SCL2/RA2_58") (pintype "bidirectional"))
    )
    (net (code "164") (name "unconnected-(IC1-SDA2{slash}RA3-Pad59)") (class "Default")
      (node (ref "IC1") (pin "59") (pinfunction "SDA2/RA3_59") (pintype "bidirectional"))
    )
    (net (code "165") (name "unconnected-(IC1-SOSCI{slash}RPC13{slash}RC13-Pad73)") (class "Default")
      (node (ref "IC1") (pin "73") (pinfunction "SOSCI/RPC13/RC13_73") (pintype "bidirectional"))
    )
    (net (code "166") (name "unconnected-(IC1-SOSCO{slash}RPC14{slash}T1CK{slash}RC14-Pad74)") (class "Default")
      (node (ref "IC1") (pin "74") (pinfunction "SOSCO/RPC14/T1CK/RC14_74") (pintype "bidirectional"))
    )
    (net (code "167") (name "unconnected-(IC1-TCK{slash}CTED2{slash}RA1-Pad38)") (class "Default")
      (node (ref "IC1") (pin "38") (pinfunction "TCK/CTED2/RA1_38") (pintype "bidirectional"))
    )
    (net (code "168") (name "unconnected-(IC1-TDI{slash}CTED9{slash}RA4-Pad60)") (class "Default")
      (node (ref "IC1") (pin "60") (pinfunction "TDI/CTED9/RA4_60") (pintype "bidirectional"))
    )
    (net (code "169") (name "unconnected-(IC1-TDO{slash}RA5-Pad61)") (class "Default")
      (node (ref "IC1") (pin "61") (pinfunction "TDO/RA5_61") (pintype "bidirectional"))
    )
    (net (code "170") (name "unconnected-(IC1-TMS{slash}CTED1{slash}RA0-Pad17)") (class "Default")
      (node (ref "IC1") (pin "17") (pinfunction "TMS/CTED1/RA0_17") (pintype "bidirectional"))
    )
    (net (code "171") (name "unconnected-(IC1-TRCLK{slash}RA6-Pad91)") (class "Default")
      (node (ref "IC1") (pin "91") (pinfunction "TRCLK/RA6_91") (pintype "bidirectional"))
    )
    (net (code "172") (name "unconnected-(IC1-TRD0{slash}RG13-Pad97)") (class "Default")
      (node (ref "IC1") (pin "97") (pinfunction "TRD0/RG13_97") (pintype "bidirectional"))
    )
    (net (code "173") (name "unconnected-(IC1-TRD2{slash}RG14-Pad95)") (class "Default")
      (node (ref "IC1") (pin "95") (pinfunction "TRD2/RG14_95") (pintype "bidirectional"))
    )
    (net (code "174") (name "unconnected-(IC1-TRD3{slash}CTED8{slash}RA7-Pad92)") (class "Default")
      (node (ref "IC1") (pin "92") (pinfunction "TRD3/CTED8/RA7_92") (pintype "bidirectional"))
    )
    (net (code "175") (name "unconnected-(IC8-PG-Pad9)") (class "Default")
      (node (ref "IC8") (pin "9") (pinfunction "PG_9") (pintype "bidirectional"))
    )
    (net (code "176") (name "unconnected-(Q1A-D-Pad6)") (class "Default")
      (node (ref "Q1") (pin "6") (pinfunction "D_6") (pintype "passive"))
    )
    (net (code "177") (name "unconnected-(Q1A-D1-PadP1)") (class "Default")
      (node (ref "Q1") (pin "P1") (pinfunction "D1_P1") (pintype "passive"))
    )
    (net (code "178") (name "unconnected-(Q1A-G-Pad2)") (class "Default")
      (node (ref "Q1") (pin "2") (pinfunction "G_2") (pintype "passive"))
    )
    (net (code "179") (name "unconnected-(Q1A-S-Pad1)") (class "Default")
      (node (ref "Q1") (pin "1") (pinfunction "S_1") (pintype "passive"))
    )
    (net (code "180") (name "unconnected-(Q2A-D-Pad6)") (class "Default")
      (node (ref "Q2") (pin "6") (pinfunction "D_6") (pintype "passive"))
    )
    (net (code "181") (name "unconnected-(Q2A-D1-PadP1)") (class "Default")
      (node (ref "Q2") (pin "P1") (pinfunction "D1_P1") (pintype "passive"))
    )
    (net (code "182") (name "unconnected-(Q2A-G-Pad2)") (class "Default")
      (node (ref "Q2") (pin "2") (pinfunction "G_2") (pintype "passive"))
    )
    (net (code "183") (name "unconnected-(Q2A-S-Pad1)") (class "Default")
      (node (ref "Q2") (pin "1") (pinfunction "S_1") (pintype "passive"))
    )
  )
)
